# untitled.net
KiCad netlist of a schematic drawn in EAGLE
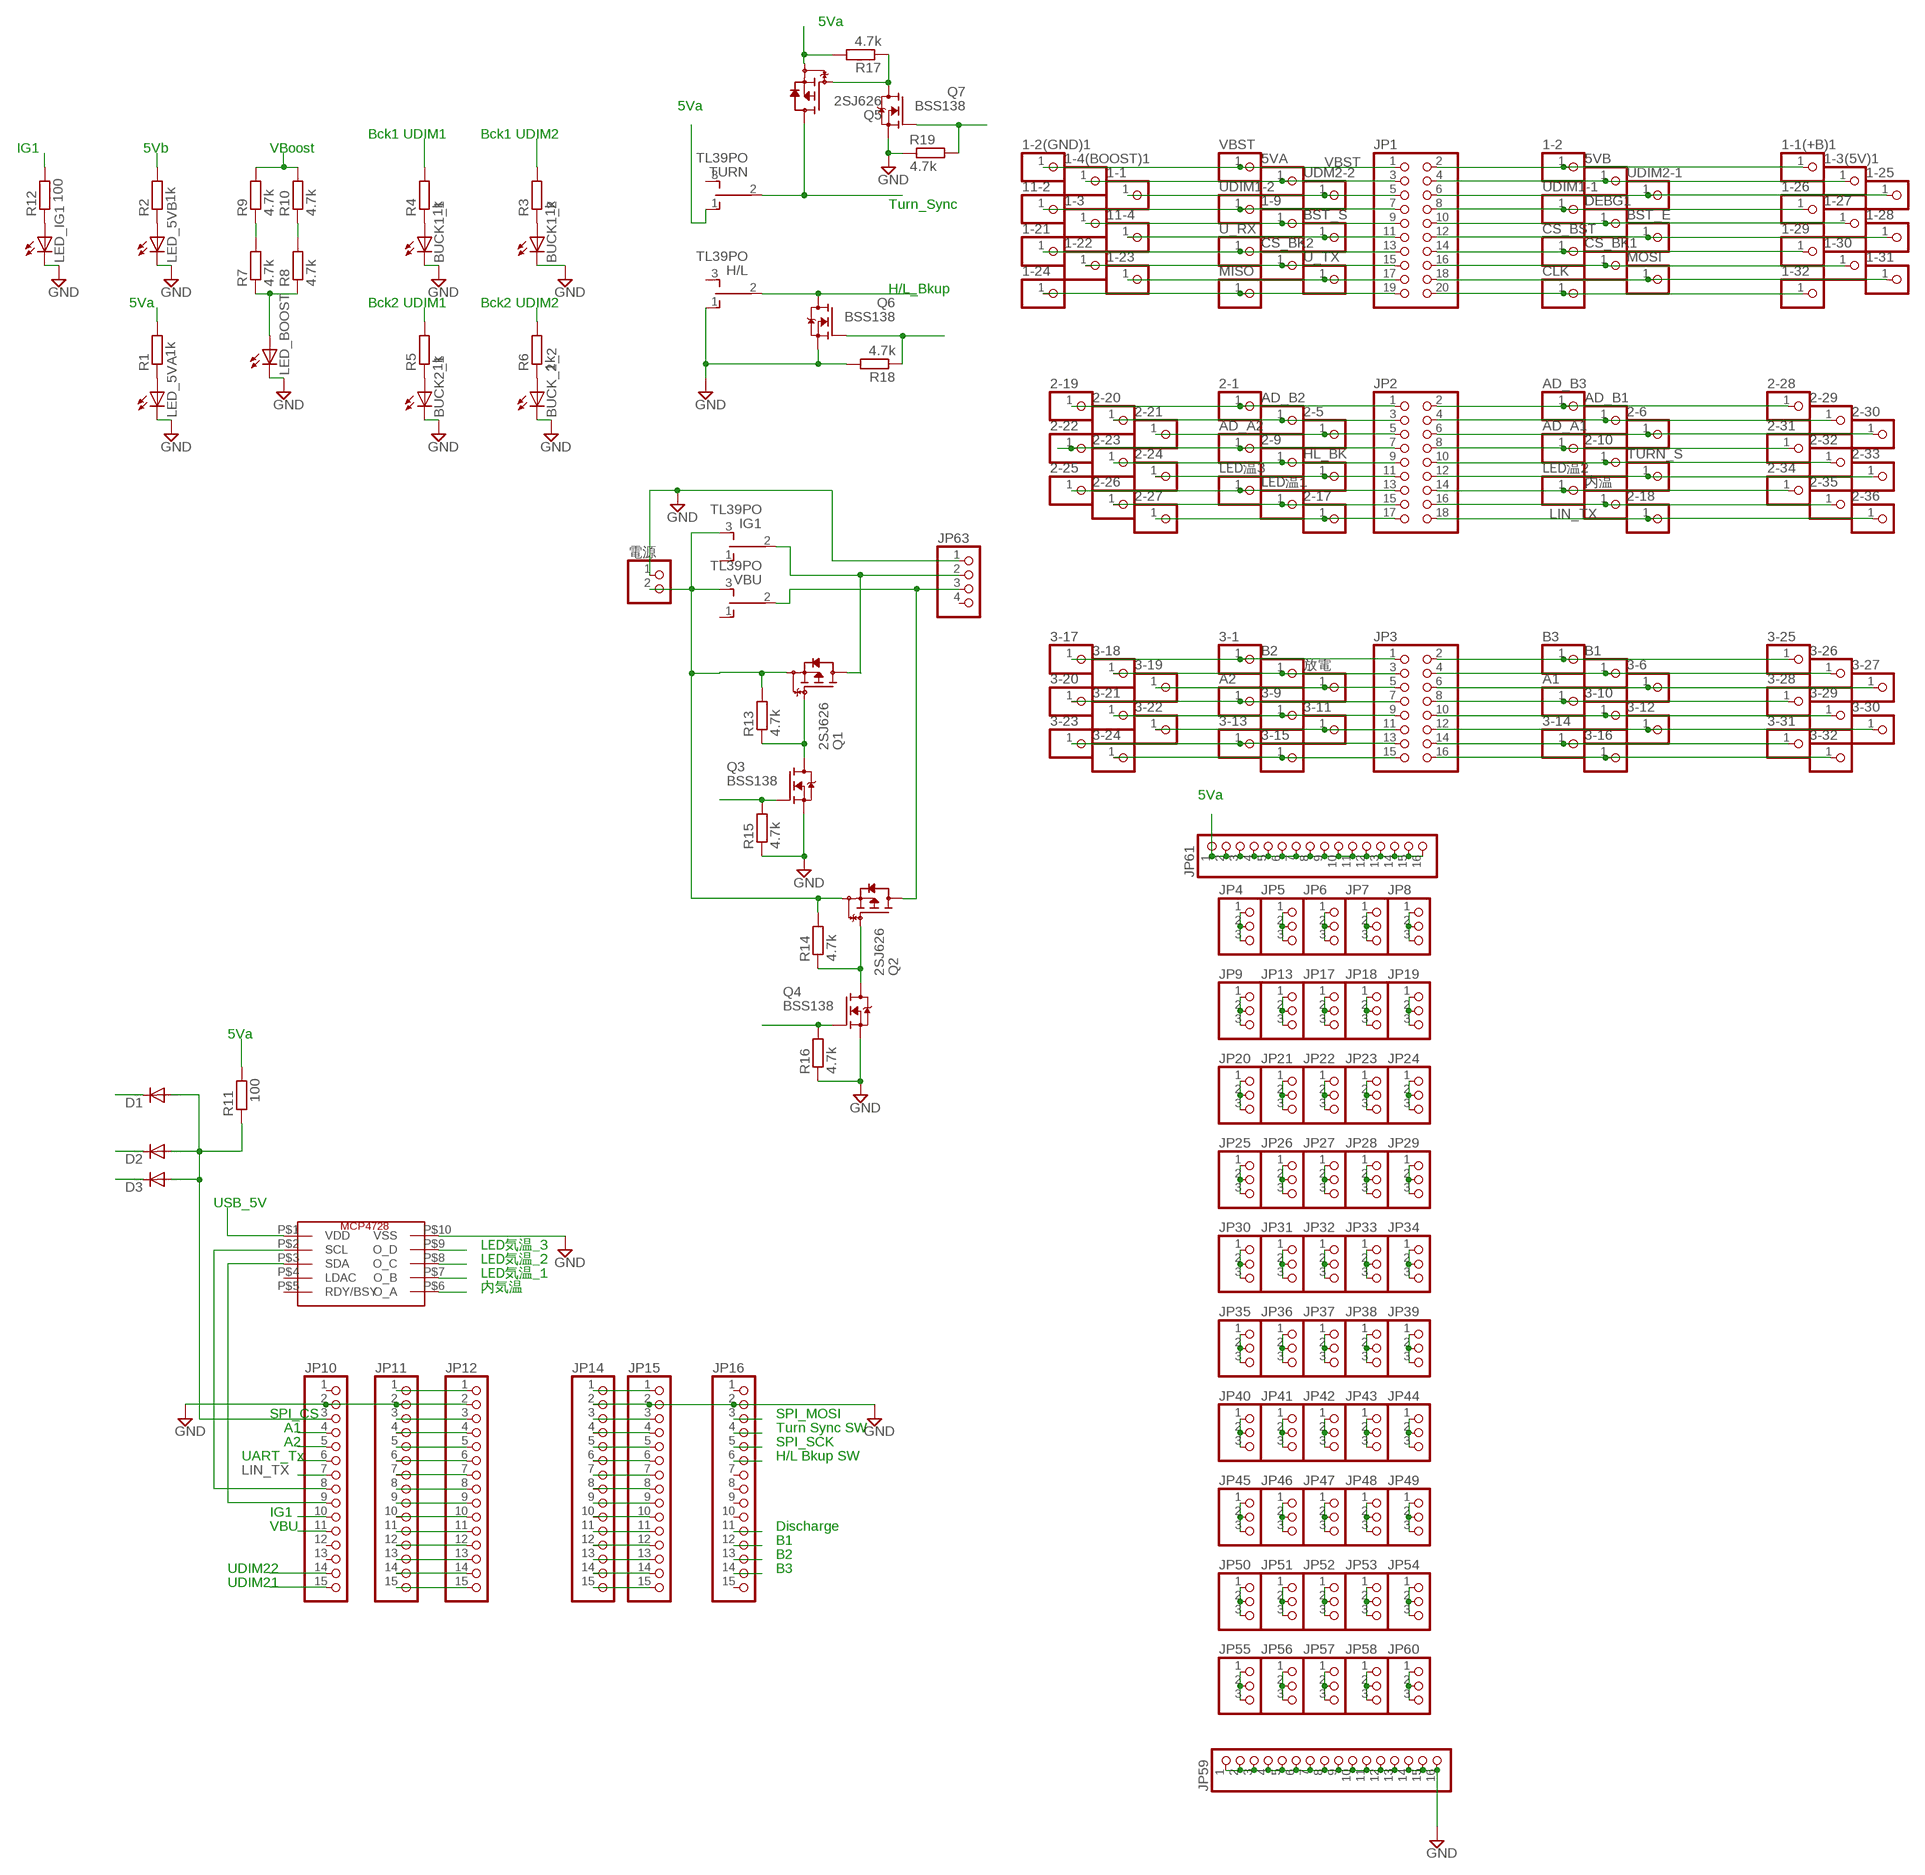
[diagram p0: schematic, sheet 1]

(export (version "E")
  (design (tool "Eeschema 10.0.6"))
  (components
    (comp (ref "1-1")
      (value "PINHD-1X1")
      (footprint "eagle-import:1X01")
      (libsource (lib "eagle-import") (part "PINHD-1X1"))
    )
    (comp (ref "1-1(+B)1")
      (value "PINHD-1X1")
      (footprint "eagle-import:1X01")
      (libsource (lib "eagle-import") (part "PINHD-1X1"))
    )
    (comp (ref "1-2")
      (value "PINHD-1X1")
      (footprint "eagle-import:1X01")
      (libsource (lib "eagle-import") (part "PINHD-1X1"))
    )
    (comp (ref "1-2(GND)1")
      (value "PINHD-1X1")
      (footprint "eagle-import:1X01")
      (libsource (lib "eagle-import") (part "PINHD-1X1"))
    )
    (comp (ref "1-3")
      (value "PINHD-1X1")
      (footprint "eagle-import:1X01")
      (libsource (lib "eagle-import") (part "PINHD-1X1"))
    )
    (comp (ref "1-3(5V)1")
      (value "PINHD-1X1")
      (footprint "eagle-import:1X01")
      (libsource (lib "eagle-import") (part "PINHD-1X1"))
    )
    (comp (ref "1-4(BOOST)1")
      (value "PINHD-1X1")
      (footprint "eagle-import:1X01")
      (libsource (lib "eagle-import") (part "PINHD-1X1"))
    )
    (comp (ref "1-9")
      (value "PINHD-1X1")
      (footprint "eagle-import:1X01")
      (libsource (lib "eagle-import") (part "PINHD-1X1"))
    )
    (comp (ref "1-21")
      (value "PINHD-1X1")
      (footprint "eagle-import:1X01")
      (libsource (lib "eagle-import") (part "PINHD-1X1"))
    )
    (comp (ref "1-22")
      (value "PINHD-1X1")
      (footprint "eagle-import:1X01")
      (libsource (lib "eagle-import") (part "PINHD-1X1"))
    )
    (comp (ref "1-23")
      (value "PINHD-1X1")
      (footprint "eagle-import:1X01")
      (libsource (lib "eagle-import") (part "PINHD-1X1"))
    )
    (comp (ref "1-24")
      (value "PINHD-1X1")
      (footprint "eagle-import:1X01")
      (libsource (lib "eagle-import") (part "PINHD-1X1"))
    )
    (comp (ref "1-25")
      (value "PINHD-1X1")
      (footprint "eagle-import:1X01")
      (libsource (lib "eagle-import") (part "PINHD-1X1"))
    )
    (comp (ref "1-26")
      (value "PINHD-1X1")
      (footprint "eagle-import:1X01")
      (libsource (lib "eagle-import") (part "PINHD-1X1"))
    )
    (comp (ref "1-27")
      (value "PINHD-1X1")
      (footprint "eagle-import:1X01")
      (libsource (lib "eagle-import") (part "PINHD-1X1"))
    )
    (comp (ref "1-28")
      (value "PINHD-1X1")
      (footprint "eagle-import:1X01")
      (libsource (lib "eagle-import") (part "PINHD-1X1"))
    )
    (comp (ref "1-29")
      (value "PINHD-1X1")
      (footprint "eagle-import:1X01")
      (libsource (lib "eagle-import") (part "PINHD-1X1"))
    )
    (comp (ref "1-30")
      (value "PINHD-1X1")
      (footprint "eagle-import:1X01")
      (libsource (lib "eagle-import") (part "PINHD-1X1"))
    )
    (comp (ref "1-31")
      (value "PINHD-1X1")
      (footprint "eagle-import:1X01")
      (libsource (lib "eagle-import") (part "PINHD-1X1"))
    )
    (comp (ref "1-32")
      (value "PINHD-1X1")
      (footprint "eagle-import:1X01")
      (libsource (lib "eagle-import") (part "PINHD-1X1"))
    )
    (comp (ref "2-1")
      (value "PINHD-1X1")
      (footprint "eagle-import:1X01")
      (libsource (lib "eagle-import") (part "PINHD-1X1"))
    )
    (comp (ref "2-5")
      (value "PINHD-1X1")
      (footprint "eagle-import:1X01")
      (libsource (lib "eagle-import") (part "PINHD-1X1"))
    )
    (comp (ref "2-6")
      (value "PINHD-1X1")
      (footprint "eagle-import:1X01")
      (libsource (lib "eagle-import") (part "PINHD-1X1"))
    )
    (comp (ref "2-9")
      (value "PINHD-1X1")
      (footprint "eagle-import:1X01")
      (libsource (lib "eagle-import") (part "PINHD-1X1"))
    )
    (comp (ref "2-10")
      (value "PINHD-1X1")
      (footprint "eagle-import:1X01")
      (libsource (lib "eagle-import") (part "PINHD-1X1"))
    )
    (comp (ref "2-17")
      (value "PINHD-1X1")
      (footprint "eagle-import:1X01")
      (libsource (lib "eagle-import") (part "PINHD-1X1"))
    )
    (comp (ref "2-18")
      (value "PINHD-1X1")
      (footprint "eagle-import:1X01")
      (libsource (lib "eagle-import") (part "PINHD-1X1"))
    )
    (comp (ref "2-19")
      (value "PINHD-1X1")
      (footprint "eagle-import:1X01")
      (libsource (lib "eagle-import") (part "PINHD-1X1"))
    )
    (comp (ref "2-20")
      (value "PINHD-1X1")
      (footprint "eagle-import:1X01")
      (libsource (lib "eagle-import") (part "PINHD-1X1"))
    )
    (comp (ref "2-21")
      (value "PINHD-1X1")
      (footprint "eagle-import:1X01")
      (libsource (lib "eagle-import") (part "PINHD-1X1"))
    )
    (comp (ref "2-22")
      (value "PINHD-1X1")
      (footprint "eagle-import:1X01")
      (libsource (lib "eagle-import") (part "PINHD-1X1"))
    )
    (comp (ref "2-23")
      (value "PINHD-1X1")
      (footprint "eagle-import:1X01")
      (libsource (lib "eagle-import") (part "PINHD-1X1"))
    )
    (comp (ref "2-24")
      (value "PINHD-1X1")
      (footprint "eagle-import:1X01")
      (libsource (lib "eagle-import") (part "PINHD-1X1"))
    )
    (comp (ref "2-25")
      (value "PINHD-1X1")
      (footprint "eagle-import:1X01")
      (libsource (lib "eagle-import") (part "PINHD-1X1"))
    )
    (comp (ref "2-26")
      (value "PINHD-1X1")
      (footprint "eagle-import:1X01")
      (libsource (lib "eagle-import") (part "PINHD-1X1"))
    )
    (comp (ref "2-27")
      (value "PINHD-1X1")
      (footprint "eagle-import:1X01")
      (libsource (lib "eagle-import") (part "PINHD-1X1"))
    )
    (comp (ref "2-28")
      (value "PINHD-1X1")
      (footprint "eagle-import:1X01")
      (libsource (lib "eagle-import") (part "PINHD-1X1"))
    )
    (comp (ref "2-29")
      (value "PINHD-1X1")
      (footprint "eagle-import:1X01")
      (libsource (lib "eagle-import") (part "PINHD-1X1"))
    )
    (comp (ref "2-30")
      (value "PINHD-1X1")
      (footprint "eagle-import:1X01")
      (libsource (lib "eagle-import") (part "PINHD-1X1"))
    )
    (comp (ref "2-31")
      (value "PINHD-1X1")
      (footprint "eagle-import:1X01")
      (libsource (lib "eagle-import") (part "PINHD-1X1"))
    )
    (comp (ref "2-32")
      (value "PINHD-1X1")
      (footprint "eagle-import:1X01")
      (libsource (lib "eagle-import") (part "PINHD-1X1"))
    )
    (comp (ref "2-33")
      (value "PINHD-1X1")
      (footprint "eagle-import:1X01")
      (libsource (lib "eagle-import") (part "PINHD-1X1"))
    )
    (comp (ref "2-34")
      (value "PINHD-1X1")
      (footprint "eagle-import:1X01")
      (libsource (lib "eagle-import") (part "PINHD-1X1"))
    )
    (comp (ref "2-35")
      (value "PINHD-1X1")
      (footprint "eagle-import:1X01")
      (libsource (lib "eagle-import") (part "PINHD-1X1"))
    )
    (comp (ref "2-36")
      (value "PINHD-1X1")
      (footprint "eagle-import:1X01")
      (libsource (lib "eagle-import") (part "PINHD-1X1"))
    )
    (comp (ref "3-1")
      (value "PINHD-1X1")
      (footprint "eagle-import:1X01")
      (libsource (lib "eagle-import") (part "PINHD-1X1"))
    )
    (comp (ref "3-6")
      (value "PINHD-1X1")
      (footprint "eagle-import:1X01")
      (libsource (lib "eagle-import") (part "PINHD-1X1"))
    )
    (comp (ref "3-9")
      (value "PINHD-1X1")
      (footprint "eagle-import:1X01")
      (libsource (lib "eagle-import") (part "PINHD-1X1"))
    )
    (comp (ref "3-10")
      (value "PINHD-1X1")
      (footprint "eagle-import:1X01")
      (libsource (lib "eagle-import") (part "PINHD-1X1"))
    )
    (comp (ref "3-11")
      (value "PINHD-1X1")
      (footprint "eagle-import:1X01")
      (libsource (lib "eagle-import") (part "PINHD-1X1"))
    )
    (comp (ref "3-12")
      (value "PINHD-1X1")
      (footprint "eagle-import:1X01")
      (libsource (lib "eagle-import") (part "PINHD-1X1"))
    )
    (comp (ref "3-13")
      (value "PINHD-1X1")
      (footprint "eagle-import:1X01")
      (libsource (lib "eagle-import") (part "PINHD-1X1"))
    )
    (comp (ref "3-14")
      (value "PINHD-1X1")
      (footprint "eagle-import:1X01")
      (libsource (lib "eagle-import") (part "PINHD-1X1"))
    )
    (comp (ref "3-15")
      (value "PINHD-1X1")
      (footprint "eagle-import:1X01")
      (libsource (lib "eagle-import") (part "PINHD-1X1"))
    )
    (comp (ref "3-16")
      (value "PINHD-1X1")
      (footprint "eagle-import:1X01")
      (libsource (lib "eagle-import") (part "PINHD-1X1"))
    )
    (comp (ref "3-17")
      (value "PINHD-1X1")
      (footprint "eagle-import:1X01")
      (libsource (lib "eagle-import") (part "PINHD-1X1"))
    )
    (comp (ref "3-18")
      (value "PINHD-1X1")
      (footprint "eagle-import:1X01")
      (libsource (lib "eagle-import") (part "PINHD-1X1"))
    )
    (comp (ref "3-19")
      (value "PINHD-1X1")
      (footprint "eagle-import:1X01")
      (libsource (lib "eagle-import") (part "PINHD-1X1"))
    )
    (comp (ref "3-20")
      (value "PINHD-1X1")
      (footprint "eagle-import:1X01")
      (libsource (lib "eagle-import") (part "PINHD-1X1"))
    )
    (comp (ref "3-21")
      (value "PINHD-1X1")
      (footprint "eagle-import:1X01")
      (libsource (lib "eagle-import") (part "PINHD-1X1"))
    )
    (comp (ref "3-22")
      (value "PINHD-1X1")
      (footprint "eagle-import:1X01")
      (libsource (lib "eagle-import") (part "PINHD-1X1"))
    )
    (comp (ref "3-23")
      (value "PINHD-1X1")
      (footprint "eagle-import:1X01")
      (libsource (lib "eagle-import") (part "PINHD-1X1"))
    )
    (comp (ref "3-24")
      (value "PINHD-1X1")
      (footprint "eagle-import:1X01")
      (libsource (lib "eagle-import") (part "PINHD-1X1"))
    )
    (comp (ref "3-25")
      (value "PINHD-1X1")
      (footprint "eagle-import:1X01")
      (libsource (lib "eagle-import") (part "PINHD-1X1"))
    )
    (comp (ref "3-26")
      (value "PINHD-1X1")
      (footprint "eagle-import:1X01")
      (libsource (lib "eagle-import") (part "PINHD-1X1"))
    )
    (comp (ref "3-27")
      (value "PINHD-1X1")
      (footprint "eagle-import:1X01")
      (libsource (lib "eagle-import") (part "PINHD-1X1"))
    )
    (comp (ref "3-28")
      (value "PINHD-1X1")
      (footprint "eagle-import:1X01")
      (libsource (lib "eagle-import") (part "PINHD-1X1"))
    )
    (comp (ref "3-29")
      (value "PINHD-1X1")
      (footprint "eagle-import:1X01")
      (libsource (lib "eagle-import") (part "PINHD-1X1"))
    )
    (comp (ref "3-30")
      (value "PINHD-1X1")
      (footprint "eagle-import:1X01")
      (libsource (lib "eagle-import") (part "PINHD-1X1"))
    )
    (comp (ref "3-31")
      (value "PINHD-1X1")
      (footprint "eagle-import:1X01")
      (libsource (lib "eagle-import") (part "PINHD-1X1"))
    )
    (comp (ref "3-32")
      (value "PINHD-1X1")
      (footprint "eagle-import:1X01")
      (libsource (lib "eagle-import") (part "PINHD-1X1"))
    )
    (comp (ref "5VA")
      (value "PINHD-1X1")
      (footprint "eagle-import:1X01")
      (libsource (lib "eagle-import") (part "PINHD-1X1"))
    )
    (comp (ref "5VB")
      (value "PINHD-1X1")
      (footprint "eagle-import:1X01")
      (libsource (lib "eagle-import") (part "PINHD-1X1"))
    )
    (comp (ref "11-2")
      (value "PINHD-1X1")
      (footprint "eagle-import:1X01")
      (libsource (lib "eagle-import") (part "PINHD-1X1"))
    )
    (comp (ref "11-4")
      (value "PINHD-1X1")
      (footprint "eagle-import:1X01")
      (libsource (lib "eagle-import") (part "PINHD-1X1"))
    )
    (comp (ref "A1")
      (value "PINHD-1X1")
      (footprint "eagle-import:1X01")
      (libsource (lib "eagle-import") (part "PINHD-1X1"))
    )
    (comp (ref "A2")
      (value "PINHD-1X1")
      (footprint "eagle-import:1X01")
      (libsource (lib "eagle-import") (part "PINHD-1X1"))
    )
    (comp (ref "AD_A1")
      (value "PINHD-1X1")
      (footprint "eagle-import:1X01")
      (libsource (lib "eagle-import") (part "PINHD-1X1"))
    )
    (comp (ref "AD_A2")
      (value "PINHD-1X1")
      (footprint "eagle-import:1X01")
      (libsource (lib "eagle-import") (part "PINHD-1X1"))
    )
    (comp (ref "AD_B1")
      (value "PINHD-1X1")
      (footprint "eagle-import:1X01")
      (libsource (lib "eagle-import") (part "PINHD-1X1"))
    )
    (comp (ref "AD_B2")
      (value "PINHD-1X1")
      (footprint "eagle-import:1X01")
      (libsource (lib "eagle-import") (part "PINHD-1X1"))
    )
    (comp (ref "AD_B3")
      (value "PINHD-1X1")
      (footprint "eagle-import:1X01")
      (libsource (lib "eagle-import") (part "PINHD-1X1"))
    )
    (comp (ref "B1")
      (value "PINHD-1X1")
      (footprint "eagle-import:1X01")
      (libsource (lib "eagle-import") (part "PINHD-1X1"))
    )
    (comp (ref "B2")
      (value "PINHD-1X1")
      (footprint "eagle-import:1X01")
      (libsource (lib "eagle-import") (part "PINHD-1X1"))
    )
    (comp (ref "B3")
      (value "PINHD-1X1")
      (footprint "eagle-import:1X01")
      (libsource (lib "eagle-import") (part "PINHD-1X1"))
    )
    (comp (ref "BST_E")
      (value "PINHD-1X1")
      (footprint "eagle-import:1X01")
      (libsource (lib "eagle-import") (part "PINHD-1X1"))
    )
    (comp (ref "BST_S")
      (value "PINHD-1X1")
      (footprint "eagle-import:1X01")
      (libsource (lib "eagle-import") (part "PINHD-1X1"))
    )
    (comp (ref "BUCK1_1")
      (value "LEDCHIP-LED0603")
      (footprint "eagle-import:CHIP-LED0603")
      (libsource (lib "eagle-import") (part "LEDCHIP-LED0603"))
    )
    (comp (ref "BUCK1_2")
      (value "LEDCHIP-LED0603")
      (footprint "eagle-import:CHIP-LED0603")
      (libsource (lib "eagle-import") (part "LEDCHIP-LED0603"))
    )
    (comp (ref "BUCK2_1")
      (value "LEDCHIP-LED0603")
      (footprint "eagle-import:CHIP-LED0603")
      (libsource (lib "eagle-import") (part "LEDCHIP-LED0603"))
    )
    (comp (ref "BUCK_2_2")
      (value "LEDCHIP-LED0603")
      (footprint "eagle-import:CHIP-LED0603")
      (libsource (lib "eagle-import") (part "LEDCHIP-LED0603"))
    )
    (comp (ref "CLK")
      (value "PINHD-1X1")
      (footprint "eagle-import:1X01")
      (libsource (lib "eagle-import") (part "PINHD-1X1"))
    )
    (comp (ref "CS_BK1")
      (value "PINHD-1X1")
      (footprint "eagle-import:1X01")
      (libsource (lib "eagle-import") (part "PINHD-1X1"))
    )
    (comp (ref "CS_BK2")
      (value "PINHD-1X1")
      (footprint "eagle-import:1X01")
      (libsource (lib "eagle-import") (part "PINHD-1X1"))
    )
    (comp (ref "CS_BST")
      (value "PINHD-1X1")
      (footprint "eagle-import:1X01")
      (libsource (lib "eagle-import") (part "PINHD-1X1"))
    )
    (comp (ref "D1")
      (value "DIODE-SOD523")
      (footprint "eagle-import:SOD523")
      (libsource (lib "eagle-import") (part "DIODE-SOD523"))
    )
    (comp (ref "D2")
      (value "DIODE-SOD523")
      (footprint "eagle-import:SOD523")
      (libsource (lib "eagle-import") (part "DIODE-SOD523"))
    )
    (comp (ref "D3")
      (value "DIODE-SOD523")
      (footprint "eagle-import:SOD523")
      (libsource (lib "eagle-import") (part "DIODE-SOD523"))
    )
    (comp (ref "DEBG1")
      (value "PINHD-1X1")
      (footprint "eagle-import:1X01")
      (libsource (lib "eagle-import") (part "PINHD-1X1"))
    )
    (comp (ref "H/L")
      (value "TL39PO")
      (footprint "eagle-import:TL3XPO")
      (libsource (lib "eagle-import") (part "TL39PO"))
    )
    (comp (ref "HL_BK")
      (value "PINHD-1X1")
      (footprint "eagle-import:1X01")
      (libsource (lib "eagle-import") (part "PINHD-1X1"))
    )
    (comp (ref "IG1")
      (value "TL39PO")
      (footprint "eagle-import:TL3XPO")
      (libsource (lib "eagle-import") (part "TL39PO"))
    )
    (comp (ref "JP1")
      (value "PINHD-2X10")
      (footprint "eagle-import:2X10")
      (libsource (lib "eagle-import") (part "PINHD-2X10"))
    )
    (comp (ref "JP2")
      (value "PINHD-2X9")
      (footprint "eagle-import:2X09")
      (libsource (lib "eagle-import") (part "PINHD-2X9"))
    )
    (comp (ref "JP3")
      (value "PINHD-2X8")
      (footprint "eagle-import:2X08")
      (libsource (lib "eagle-import") (part "PINHD-2X8"))
    )
    (comp (ref "JP4")
      (value "PINHD-1X3")
      (footprint "eagle-import:1X03")
      (libsource (lib "eagle-import") (part "PINHD-1X3"))
    )
    (comp (ref "JP5")
      (value "PINHD-1X3")
      (footprint "eagle-import:1X03")
      (libsource (lib "eagle-import") (part "PINHD-1X3"))
    )
    (comp (ref "JP6")
      (value "PINHD-1X3")
      (footprint "eagle-import:1X03")
      (libsource (lib "eagle-import") (part "PINHD-1X3"))
    )
    (comp (ref "JP7")
      (value "PINHD-1X3")
      (footprint "eagle-import:1X03")
      (libsource (lib "eagle-import") (part "PINHD-1X3"))
    )
    (comp (ref "JP8")
      (value "PINHD-1X3")
      (footprint "eagle-import:1X03")
      (libsource (lib "eagle-import") (part "PINHD-1X3"))
    )
    (comp (ref "JP9")
      (value "PINHD-1X3")
      (footprint "eagle-import:1X03")
      (libsource (lib "eagle-import") (part "PINHD-1X3"))
    )
    (comp (ref "JP10")
      (value "PINHD-1X15")
      (footprint "eagle-import:1X15")
      (libsource (lib "eagle-import") (part "PINHD-1X15"))
    )
    (comp (ref "JP11")
      (value "PINHD-1X15")
      (footprint "eagle-import:1X15")
      (libsource (lib "eagle-import") (part "PINHD-1X15"))
    )
    (comp (ref "JP12")
      (value "PINHD-1X15")
      (footprint "eagle-import:1X15")
      (libsource (lib "eagle-import") (part "PINHD-1X15"))
    )
    (comp (ref "JP13")
      (value "PINHD-1X3")
      (footprint "eagle-import:1X03")
      (libsource (lib "eagle-import") (part "PINHD-1X3"))
    )
    (comp (ref "JP14")
      (value "PINHD-1X15")
      (footprint "eagle-import:1X15")
      (libsource (lib "eagle-import") (part "PINHD-1X15"))
    )
    (comp (ref "JP15")
      (value "PINHD-1X15")
      (footprint "eagle-import:1X15")
      (libsource (lib "eagle-import") (part "PINHD-1X15"))
    )
    (comp (ref "JP16")
      (value "PINHD-1X15")
      (footprint "eagle-import:1X15")
      (libsource (lib "eagle-import") (part "PINHD-1X15"))
    )
    (comp (ref "JP17")
      (value "PINHD-1X3")
      (footprint "eagle-import:1X03")
      (libsource (lib "eagle-import") (part "PINHD-1X3"))
    )
    (comp (ref "JP18")
      (value "PINHD-1X3")
      (footprint "eagle-import:1X03")
      (libsource (lib "eagle-import") (part "PINHD-1X3"))
    )
    (comp (ref "JP19")
      (value "PINHD-1X3")
      (footprint "eagle-import:1X03")
      (libsource (lib "eagle-import") (part "PINHD-1X3"))
    )
    (comp (ref "JP20")
      (value "PINHD-1X3")
      (footprint "eagle-import:1X03")
      (libsource (lib "eagle-import") (part "PINHD-1X3"))
    )
    (comp (ref "JP21")
      (value "PINHD-1X3")
      (footprint "eagle-import:1X03")
      (libsource (lib "eagle-import") (part "PINHD-1X3"))
    )
    (comp (ref "JP22")
      (value "PINHD-1X3")
      (footprint "eagle-import:1X03")
      (libsource (lib "eagle-import") (part "PINHD-1X3"))
    )
    (comp (ref "JP23")
      (value "PINHD-1X3")
      (footprint "eagle-import:1X03")
      (libsource (lib "eagle-import") (part "PINHD-1X3"))
    )
    (comp (ref "JP24")
      (value "PINHD-1X3")
      (footprint "eagle-import:1X03")
      (libsource (lib "eagle-import") (part "PINHD-1X3"))
    )
    (comp (ref "JP25")
      (value "PINHD-1X3")
      (footprint "eagle-import:1X03")
      (libsource (lib "eagle-import") (part "PINHD-1X3"))
    )
    (comp (ref "JP26")
      (value "PINHD-1X3")
      (footprint "eagle-import:1X03")
      (libsource (lib "eagle-import") (part "PINHD-1X3"))
    )
    (comp (ref "JP27")
      (value "PINHD-1X3")
      (footprint "eagle-import:1X03")
      (libsource (lib "eagle-import") (part "PINHD-1X3"))
    )
    (comp (ref "JP28")
      (value "PINHD-1X3")
      (footprint "eagle-import:1X03")
      (libsource (lib "eagle-import") (part "PINHD-1X3"))
    )
    (comp (ref "JP29")
      (value "PINHD-1X3")
      (footprint "eagle-import:1X03")
      (libsource (lib "eagle-import") (part "PINHD-1X3"))
    )
    (comp (ref "JP30")
      (value "PINHD-1X3")
      (footprint "eagle-import:1X03")
      (libsource (lib "eagle-import") (part "PINHD-1X3"))
    )
    (comp (ref "JP31")
      (value "PINHD-1X3")
      (footprint "eagle-import:1X03")
      (libsource (lib "eagle-import") (part "PINHD-1X3"))
    )
    (comp (ref "JP32")
      (value "PINHD-1X3")
      (footprint "eagle-import:1X03")
      (libsource (lib "eagle-import") (part "PINHD-1X3"))
    )
    (comp (ref "JP33")
      (value "PINHD-1X3")
      (footprint "eagle-import:1X03")
      (libsource (lib "eagle-import") (part "PINHD-1X3"))
    )
    (comp (ref "JP34")
      (value "PINHD-1X3")
      (footprint "eagle-import:1X03")
      (libsource (lib "eagle-import") (part "PINHD-1X3"))
    )
    (comp (ref "JP35")
      (value "PINHD-1X3")
      (footprint "eagle-import:1X03")
      (libsource (lib "eagle-import") (part "PINHD-1X3"))
    )
    (comp (ref "JP36")
      (value "PINHD-1X3")
      (footprint "eagle-import:1X03")
      (libsource (lib "eagle-import") (part "PINHD-1X3"))
    )
    (comp (ref "JP37")
      (value "PINHD-1X3")
      (footprint "eagle-import:1X03")
      (libsource (lib "eagle-import") (part "PINHD-1X3"))
    )
    (comp (ref "JP38")
      (value "PINHD-1X3")
      (footprint "eagle-import:1X03")
      (libsource (lib "eagle-import") (part "PINHD-1X3"))
    )
    (comp (ref "JP39")
      (value "PINHD-1X3")
      (footprint "eagle-import:1X03")
      (libsource (lib "eagle-import") (part "PINHD-1X3"))
    )
    (comp (ref "JP40")
      (value "PINHD-1X3")
      (footprint "eagle-import:1X03")
      (libsource (lib "eagle-import") (part "PINHD-1X3"))
    )
    (comp (ref "JP41")
      (value "PINHD-1X3")
      (footprint "eagle-import:1X03")
      (libsource (lib "eagle-import") (part "PINHD-1X3"))
    )
    (comp (ref "JP42")
      (value "PINHD-1X3")
      (footprint "eagle-import:1X03")
      (libsource (lib "eagle-import") (part "PINHD-1X3"))
    )
    (comp (ref "JP43")
      (value "PINHD-1X3")
      (footprint "eagle-import:1X03")
      (libsource (lib "eagle-import") (part "PINHD-1X3"))
    )
    (comp (ref "JP44")
      (value "PINHD-1X3")
      (footprint "eagle-import:1X03")
      (libsource (lib "eagle-import") (part "PINHD-1X3"))
    )
    (comp (ref "JP45")
      (value "PINHD-1X3")
      (footprint "eagle-import:1X03")
      (libsource (lib "eagle-import") (part "PINHD-1X3"))
    )
    (comp (ref "JP46")
      (value "PINHD-1X3")
      (footprint "eagle-import:1X03")
      (libsource (lib "eagle-import") (part "PINHD-1X3"))
    )
    (comp (ref "JP47")
      (value "PINHD-1X3")
      (footprint "eagle-import:1X03")
      (libsource (lib "eagle-import") (part "PINHD-1X3"))
    )
    (comp (ref "JP48")
      (value "PINHD-1X3")
      (footprint "eagle-import:1X03")
      (libsource (lib "eagle-import") (part "PINHD-1X3"))
    )
    (comp (ref "JP49")
      (value "PINHD-1X3")
      (footprint "eagle-import:1X03")
      (libsource (lib "eagle-import") (part "PINHD-1X3"))
    )
    (comp (ref "JP50")
      (value "PINHD-1X3")
      (footprint "eagle-import:1X03")
      (libsource (lib "eagle-import") (part "PINHD-1X3"))
    )
    (comp (ref "JP51")
      (value "PINHD-1X3")
      (footprint "eagle-import:1X03")
      (libsource (lib "eagle-import") (part "PINHD-1X3"))
    )
    (comp (ref "JP52")
      (value "PINHD-1X3")
      (footprint "eagle-import:1X03")
      (libsource (lib "eagle-import") (part "PINHD-1X3"))
    )
    (comp (ref "JP53")
      (value "PINHD-1X3")
      (footprint "eagle-import:1X03")
      (libsource (lib "eagle-import") (part "PINHD-1X3"))
    )
    (comp (ref "JP54")
      (value "PINHD-1X3")
      (footprint "eagle-import:1X03")
      (libsource (lib "eagle-import") (part "PINHD-1X3"))
    )
    (comp (ref "JP55")
      (value "PINHD-1X3")
      (footprint "eagle-import:1X03")
      (libsource (lib "eagle-import") (part "PINHD-1X3"))
    )
    (comp (ref "JP56")
      (value "PINHD-1X3")
      (footprint "eagle-import:1X03")
      (libsource (lib "eagle-import") (part "PINHD-1X3"))
    )
    (comp (ref "JP57")
      (value "PINHD-1X3")
      (footprint "eagle-import:1X03")
      (libsource (lib "eagle-import") (part "PINHD-1X3"))
    )
    (comp (ref "JP58")
      (value "PINHD-1X3")
      (footprint "eagle-import:1X03")
      (libsource (lib "eagle-import") (part "PINHD-1X3"))
    )
    (comp (ref "JP59")
      (value "PINHD-1X16")
      (footprint "eagle-import:1X16")
      (libsource (lib "eagle-import") (part "PINHD-1X16"))
    )
    (comp (ref "JP60")
      (value "PINHD-1X3")
      (footprint "eagle-import:1X03")
      (libsource (lib "eagle-import") (part "PINHD-1X3"))
    )
    (comp (ref "JP61")
      (value "PINHD-1X16")
      (footprint "eagle-import:1X16")
      (libsource (lib "eagle-import") (part "PINHD-1X16"))
    )
    (comp (ref "JP63")
      (value "PINHD-1X4")
      (footprint "eagle-import:1X04")
      (libsource (lib "eagle-import") (part "PINHD-1X4"))
    )
    (comp (ref "LED_5VA")
      (value "LEDCHIP-LED0603")
      (footprint "eagle-import:CHIP-LED0603")
      (libsource (lib "eagle-import") (part "LEDCHIP-LED0603"))
    )
    (comp (ref "LED_5VB")
      (value "LEDCHIP-LED0603")
      (footprint "eagle-import:CHIP-LED0603")
      (libsource (lib "eagle-import") (part "LEDCHIP-LED0603"))
    )
    (comp (ref "LED_BOOST")
      (value "LEDCHIP-LED0603")
      (footprint "eagle-import:CHIP-LED0603")
      (libsource (lib "eagle-import") (part "LEDCHIP-LED0603"))
    )
    (comp (ref "LED_IG1")
      (value "LEDCHIP-LED0603")
      (footprint "eagle-import:CHIP-LED0603")
      (libsource (lib "eagle-import") (part "LEDCHIP-LED0603"))
    )
    (comp (ref "LED温1")
      (value "PINHD-1X1")
      (footprint "eagle-import:1X01")
      (libsource (lib "eagle-import") (part "PINHD-1X1"))
    )
    (comp (ref "LED温2")
      (value "PINHD-1X1")
      (footprint "eagle-import:1X01")
      (libsource (lib "eagle-import") (part "PINHD-1X1"))
    )
    (comp (ref "LED温3")
      (value "PINHD-1X1")
      (footprint "eagle-import:1X01")
      (libsource (lib "eagle-import") (part "PINHD-1X1"))
    )
    (comp (ref "MISO")
      (value "PINHD-1X1")
      (footprint "eagle-import:1X01")
      (libsource (lib "eagle-import") (part "PINHD-1X1"))
    )
    (comp (ref "MOSI")
      (value "PINHD-1X1")
      (footprint "eagle-import:1X01")
      (libsource (lib "eagle-import") (part "PINHD-1X1"))
    )
    (comp (ref "Q1")
      (value "2SJ626")
      (footprint "eagle-import:SOT23")
      (fields (field (name "MF") "Fairchild"))
      (libsource (lib "eagle-import") (part "2SJ626"))
    )
    (comp (ref "Q2")
      (value "2SJ626")
      (footprint "eagle-import:SOT23")
      (fields (field (name "MF") "Fairchild"))
      (libsource (lib "eagle-import") (part "2SJ626"))
    )
    (comp (ref "Q3")
      (value "BSS138")
      (footprint "eagle-import:SOT23")
      (fields (field (name "MF") "Fairchild"))
      (libsource (lib "eagle-import") (part "BSS138"))
    )
    (comp (ref "Q4")
      (value "BSS138")
      (footprint "eagle-import:SOT23")
      (fields (field (name "MF") "Fairchild"))
      (libsource (lib "eagle-import") (part "BSS138"))
    )
    (comp (ref "Q5")
      (value "2SJ626")
      (footprint "eagle-import:SOT23")
      (fields (field (name "MF") "Fairchild"))
      (libsource (lib "eagle-import") (part "2SJ626"))
    )
    (comp (ref "Q6")
      (value "BSS138")
      (footprint "eagle-import:SOT23")
      (fields (field (name "MF") "Fairchild"))
      (libsource (lib "eagle-import") (part "BSS138"))
    )
    (comp (ref "Q7")
      (value "BSS138")
      (footprint "eagle-import:SOT23")
      (fields (field (name "MF") "Fairchild"))
      (libsource (lib "eagle-import") (part "BSS138"))
    )
    (comp (ref "R1")
      (value "1k")
      (footprint "eagle-import:R0603")
      (libsource (lib "eagle-import") (part "R-EU_R0603"))
    )
    (comp (ref "R2")
      (value "1k")
      (footprint "eagle-import:R0603")
      (libsource (lib "eagle-import") (part "R-EU_R0603"))
    )
    (comp (ref "R3")
      (value "1k")
      (footprint "eagle-import:R0603")
      (libsource (lib "eagle-import") (part "R-EU_R0603"))
    )
    (comp (ref "R4")
      (value "1k")
      (footprint "eagle-import:R0603")
      (libsource (lib "eagle-import") (part "R-EU_R0603"))
    )
    (comp (ref "R5")
      (value "1k")
      (footprint "eagle-import:R0603")
      (libsource (lib "eagle-import") (part "R-EU_R0603"))
    )
    (comp (ref "R6")
      (value "1k")
      (footprint "eagle-import:R0603")
      (libsource (lib "eagle-import") (part "R-EU_R0603"))
    )
    (comp (ref "R7")
      (value "4.7k")
      (footprint "eagle-import:R0603")
      (libsource (lib "eagle-import") (part "R-EU_R0603"))
    )
    (comp (ref "R8")
      (value "4.7k")
      (footprint "eagle-import:R0603")
      (libsource (lib "eagle-import") (part "R-EU_R0603"))
    )
    (comp (ref "R9")
      (value "4.7k")
      (footprint "eagle-import:R0603")
      (libsource (lib "eagle-import") (part "R-EU_R0603"))
    )
    (comp (ref "R10")
      (value "4.7k")
      (footprint "eagle-import:R0603")
      (libsource (lib "eagle-import") (part "R-EU_R0603"))
    )
    (comp (ref "R11")
      (value "100")
      (footprint "eagle-import:R0603")
      (libsource (lib "eagle-import") (part "R-EU_R0603"))
    )
    (comp (ref "R12")
      (value "100")
      (footprint "eagle-import:R0603")
      (libsource (lib "eagle-import") (part "R-EU_R0603"))
    )
    (comp (ref "R13")
      (value "4.7k")
      (footprint "eagle-import:R0603")
      (libsource (lib "eagle-import") (part "R-EU_R0603"))
    )
    (comp (ref "R14")
      (value "4.7k")
      (footprint "eagle-import:R0603")
      (libsource (lib "eagle-import") (part "R-EU_R0603"))
    )
    (comp (ref "R15")
      (value "4.7k")
      (footprint "eagle-import:R0603")
      (libsource (lib "eagle-import") (part "R-EU_R0603"))
    )
    (comp (ref "R16")
      (value "4.7k")
      (footprint "eagle-import:R0603")
      (libsource (lib "eagle-import") (part "R-EU_R0603"))
    )
    (comp (ref "R17")
      (value "4.7k")
      (footprint "eagle-import:R0603")
      (libsource (lib "eagle-import") (part "R-EU_R0603"))
    )
    (comp (ref "R18")
      (value "4.7k")
      (footprint "eagle-import:R0603")
      (libsource (lib "eagle-import") (part "R-EU_R0603"))
    )
    (comp (ref "R19")
      (value "4.7k")
      (footprint "eagle-import:R0603")
      (libsource (lib "eagle-import") (part "R-EU_R0603"))
    )
    (comp (ref "TURN")
      (value "TL39PO")
      (footprint "eagle-import:TL3XPO")
      (libsource (lib "eagle-import") (part "TL39PO"))
    )
    (comp (ref "TURN_S")
      (value "PINHD-1X1")
      (footprint "eagle-import:1X01")
      (libsource (lib "eagle-import") (part "PINHD-1X1"))
    )
    (comp (ref "U$1")
      (value "MCP4728")
      (footprint "eagle-import:MCP4728")
      (libsource (lib "eagle-import") (part "MCP4728"))
    )
    (comp (ref "UDIM1-1")
      (value "PINHD-1X1")
      (footprint "eagle-import:1X01")
      (libsource (lib "eagle-import") (part "PINHD-1X1"))
    )
    (comp (ref "UDIM1-2")
      (value "PINHD-1X1")
      (footprint "eagle-import:1X01")
      (libsource (lib "eagle-import") (part "PINHD-1X1"))
    )
    (comp (ref "UDIM2-1")
      (value "PINHD-1X1")
      (footprint "eagle-import:1X01")
      (libsource (lib "eagle-import") (part "PINHD-1X1"))
    )
    (comp (ref "UDM2-2")
      (value "PINHD-1X1")
      (footprint "eagle-import:1X01")
      (libsource (lib "eagle-import") (part "PINHD-1X1"))
    )
    (comp (ref "U_RX")
      (value "PINHD-1X1")
      (footprint "eagle-import:1X01")
      (libsource (lib "eagle-import") (part "PINHD-1X1"))
    )
    (comp (ref "U_TX")
      (value "PINHD-1X1")
      (footprint "eagle-import:1X01")
      (libsource (lib "eagle-import") (part "PINHD-1X1"))
    )
    (comp (ref "VBST")
      (value "PINHD-1X1")
      (footprint "eagle-import:1X01")
      (libsource (lib "eagle-import") (part "PINHD-1X1"))
    )
    (comp (ref "VBU")
      (value "TL39PO")
      (footprint "eagle-import:TL3XPO")
      (libsource (lib "eagle-import") (part "TL39PO"))
    )
    (comp (ref "内温")
      (value "PINHD-1X1")
      (footprint "eagle-import:1X01")
      (libsource (lib "eagle-import") (part "PINHD-1X1"))
    )
    (comp (ref "放電")
      (value "PINHD-1X1")
      (footprint "eagle-import:1X01")
      (libsource (lib "eagle-import") (part "PINHD-1X1"))
    )
    (comp (ref "電源")
      (value "PINHD-1X2")
      (footprint "eagle-import:1X02")
      (libsource (lib "eagle-import") (part "PINHD-1X2"))
    )
  )
  (nets
    (net (code "1") (name "/+B(電源)") (class "Default")
      (node (ref "IG1") (pin "3") (pinfunction "S_3") (pintype "passive"))
      (node (ref "Q1") (pin "2") (pinfunction "S_2") (pintype "passive"))
      (node (ref "Q2") (pin "2") (pinfunction "S_2") (pintype "passive"))
      (node (ref "R13") (pin "2") (pinfunction "2_2") (pintype "passive"))
      (node (ref "R14") (pin "2") (pinfunction "2_2") (pintype "passive"))
      (node (ref "VBU") (pin "3") (pinfunction "S_3") (pintype "passive"))
      (node (ref "電源") (pin "2") (pinfunction "2_2") (pintype "passive"))
    )
    (net (code "2") (name "/5VA") (class "Default")
      (node (ref "1-4(BOOST)1") (pin "1") (pinfunction "1_1") (pintype "passive"))
      (node (ref "5VA") (pin "1") (pinfunction "1_1") (pintype "passive"))
      (node (ref "JP1") (pin "3") (pinfunction "3_3") (pintype "passive"))
      (node (ref "JP61") (pin "1") (pinfunction "1_1") (pintype "passive"))
      (node (ref "JP61") (pin "10") (pinfunction "10_10") (pintype "passive"))
      (node (ref "JP61") (pin "11") (pinfunction "11_11") (pintype "passive"))
      (node (ref "JP61") (pin "12") (pinfunction "12_12") (pintype "passive"))
      (node (ref "JP61") (pin "13") (pinfunction "13_13") (pintype "passive"))
      (node (ref "JP61") (pin "14") (pinfunction "14_14") (pintype "passive"))
      (node (ref "JP61") (pin "15") (pinfunction "15_15") (pintype "passive"))
      (node (ref "JP61") (pin "16") (pinfunction "16_16") (pintype "passive"))
      (node (ref "JP61") (pin "2") (pinfunction "2_2") (pintype "passive"))
      (node (ref "JP61") (pin "3") (pinfunction "3_3") (pintype "passive"))
      (node (ref "JP61") (pin "4") (pinfunction "4_4") (pintype "passive"))
      (node (ref "JP61") (pin "5") (pinfunction "5_5") (pintype "passive"))
      (node (ref "JP61") (pin "6") (pinfunction "6_6") (pintype "passive"))
      (node (ref "JP61") (pin "7") (pinfunction "7_7") (pintype "passive"))
      (node (ref "JP61") (pin "8") (pinfunction "8_8") (pintype "passive"))
      (node (ref "JP61") (pin "9") (pinfunction "9_9") (pintype "passive"))
      (node (ref "Q5") (pin "2") (pinfunction "S_2") (pintype "passive"))
      (node (ref "R1") (pin "2") (pinfunction "2_2") (pintype "passive"))
      (node (ref "R11") (pin "2") (pinfunction "2_2") (pintype "passive"))
      (node (ref "R17") (pin "2") (pinfunction "2_2") (pintype "passive"))
      (node (ref "TURN") (pin "1") (pinfunction "O_1") (pintype "passive"))
    )
    (net (code "3") (name "/5VB") (class "Default")
      (node (ref "1-3(5V)1") (pin "1") (pinfunction "1_1") (pintype "passive"))
      (node (ref "5VB") (pin "1") (pinfunction "1_1") (pintype "passive"))
      (node (ref "JP1") (pin "4") (pinfunction "4_4") (pintype "passive"))
      (node (ref "R2") (pin "2") (pinfunction "2_2") (pintype "passive"))
    )
    (net (code "4") (name "/A1") (class "Default")
      (node (ref "3-28") (pin "1") (pinfunction "1_1") (pintype "passive"))
      (node (ref "A1") (pin "1") (pinfunction "1_1") (pintype "passive"))
      (node (ref "JP10") (pin "4") (pinfunction "4_4") (pintype "passive"))
      (node (ref "JP3") (pin "8") (pinfunction "8_8") (pintype "passive"))
    )
    (net (code "5") (name "/A2") (class "Default")
      (node (ref "3-20") (pin "1") (pinfunction "1_1") (pintype "passive"))
      (node (ref "A2") (pin "1") (pinfunction "1_1") (pintype "passive"))
      (node (ref "JP10") (pin "5") (pinfunction "5_5") (pintype "passive"))
      (node (ref "JP3") (pin "7") (pinfunction "7_7") (pintype "passive"))
    )
    (net (code "6") (name "/B1") (class "Default")
      (node (ref "3-26") (pin "1") (pinfunction "1_1") (pintype "passive"))
      (node (ref "B1") (pin "1") (pinfunction "1_1") (pintype "passive"))
      (node (ref "JP16") (pin "12") (pinfunction "12_12") (pintype "passive"))
      (node (ref "JP3") (pin "4") (pinfunction "4_4") (pintype "passive"))
    )
    (net (code "7") (name "/B2") (class "Default")
      (node (ref "3-18") (pin "1") (pinfunction "1_1") (pintype "passive"))
      (node (ref "B2") (pin "1") (pinfunction "1_1") (pintype "passive"))
      (node (ref "JP16") (pin "13") (pinfunction "13_13") (pintype "passive"))
      (node (ref "JP3") (pin "3") (pinfunction "3_3") (pintype "passive"))
    )
    (net (code "8") (name "/B3") (class "Default")
      (node (ref "3-25") (pin "1") (pinfunction "1_1") (pintype "passive"))
      (node (ref "B3") (pin "1") (pinfunction "1_1") (pintype "passive"))
      (node (ref "JP16") (pin "14") (pinfunction "14_14") (pintype "passive"))
      (node (ref "JP3") (pin "2") (pinfunction "2_2") (pintype "passive"))
    )
    (net (code "9") (name "/BCK1UDIM1") (class "Default")
      (node (ref "1-26") (pin "1") (pinfunction "1_1") (pintype "passive"))
      (node (ref "JP1") (pin "8") (pinfunction "8_8") (pintype "passive"))
      (node (ref "R4") (pin "2") (pinfunction "2_2") (pintype "passive"))
      (node (ref "UDIM1-1") (pin "1") (pinfunction "1_1") (pintype "passive"))
    )
    (net (code "10") (name "/BCK1UDIM2") (class "Default")
      (node (ref "11-2") (pin "1") (pinfunction "1_1") (pintype "passive"))
      (node (ref "JP1") (pin "7") (pinfunction "7_7") (pintype "passive"))
      (node (ref "R3") (pin "2") (pinfunction "2_2") (pintype "passive"))
      (node (ref "UDIM1-2") (pin "1") (pinfunction "1_1") (pintype "passive"))
    )
    (net (code "11") (name "/BCK2UDIM1") (class "Default")
      (node (ref "1-25") (pin "1") (pinfunction "1_1") (pintype "passive"))
      (node (ref "JP1") (pin "6") (pinfunction "6_6") (pintype "passive"))
      (node (ref "JP10") (pin "15") (pinfunction "15_15") (pintype "passive"))
      (node (ref "R5") (pin "2") (pinfunction "2_2") (pintype "passive"))
      (node (ref "UDIM2-1") (pin "1") (pinfunction "1_1") (pintype "passive"))
    )
    (net (code "12") (name "/BCK2UDIM2") (class "Default")
      (node (ref "1-1") (pin "1") (pinfunction "1_1") (pintype "passive"))
      (node (ref "JP1") (pin "5") (pinfunction "5_5") (pintype "passive"))
      (node (ref "JP10") (pin "14") (pinfunction "14_14") (pintype "passive"))
      (node (ref "R6") (pin "2") (pinfunction "2_2") (pintype "passive"))
      (node (ref "UDM2-2") (pin "1") (pinfunction "1_1") (pintype "passive"))
    )
    (net (code "13") (name "/DISCHARGE") (class "Default")
      (node (ref "3-19") (pin "1") (pinfunction "1_1") (pintype "passive"))
      (node (ref "JP16") (pin "11") (pinfunction "11_11") (pintype "passive"))
      (node (ref "JP3") (pin "5") (pinfunction "5_5") (pintype "passive"))
      (node (ref "放電") (pin "1") (pinfunction "1_1") (pintype "passive"))
    )
    (net (code "14") (name "/ESP32_HL_BKUP") (class "Default")
      (node (ref "JP16") (pin "6") (pinfunction "6_6") (pintype "passive"))
      (node (ref "Q6") (pin "1") (pinfunction "G_1") (pintype "passive"))
      (node (ref "R18") (pin "1") (pinfunction "1_1") (pintype "passive"))
    )
    (net (code "15") (name "/ESP32_TURN_SYNC") (class "Default")
      (node (ref "JP16") (pin "4") (pinfunction "4_4") (pintype "passive"))
      (node (ref "Q7") (pin "1") (pinfunction "G_1") (pintype "passive"))
      (node (ref "R19") (pin "2") (pinfunction "2_2") (pintype "passive"))
    )
    (net (code "16") (name "/ESP_IG1_SW") (class "Default")
      (node (ref "JP10") (pin "10") (pinfunction "10_10") (pintype "passive"))
      (node (ref "Q3") (pin "1") (pinfunction "G_1") (pintype "passive"))
      (node (ref "R15") (pin "2") (pinfunction "2_2") (pintype "passive"))
    )
    (net (code "17") (name "/ESP_VBU_SW") (class "Default")
      (node (ref "JP10") (pin "11") (pinfunction "11_11") (pintype "passive"))
      (node (ref "Q4") (pin "1") (pinfunction "G_1") (pintype "passive"))
      (node (ref "R16") (pin "2") (pinfunction "2_2") (pintype "passive"))
    )
    (net (code "18") (name "/HL_BKUP") (class "Default")
      (node (ref "2-24") (pin "1") (pinfunction "1_1") (pintype "passive"))
      (node (ref "H/L") (pin "2") (pinfunction "P_2") (pintype "passive"))
      (node (ref "HL_BK") (pin "1") (pinfunction "1_1") (pintype "passive"))
      (node (ref "JP2") (pin "11") (pinfunction "11_11") (pintype "passive"))
      (node (ref "Q6") (pin "3") (pinfunction "D_3") (pintype "passive"))
    )
    (net (code "19") (name "/IG1") (class "Default")
      (node (ref "IG1") (pin "2") (pinfunction "P_2") (pintype "passive"))
      (node (ref "JP63") (pin "2") (pinfunction "2_2") (pintype "passive"))
      (node (ref "Q1") (pin "3") (pinfunction "D_3") (pintype "passive"))
      (node (ref "R12") (pin "2") (pinfunction "2_2") (pintype "passive"))
    )
    (net (code "20") (name "/INSIDE_THM") (class "Default")
      (node (ref "2-35") (pin "1") (pinfunction "1_1") (pintype "passive"))
      (node (ref "JP2") (pin "16") (pinfunction "16_16") (pintype "passive"))
      (node (ref "U$1") (pin "P$6") (pinfunction "O_A_P$6") (pintype "bidirectional"))
      (node (ref "内温") (pin "1") (pinfunction "1_1") (pintype "passive"))
    )
    (net (code "21") (name "/LED_THM1") (class "Default")
      (node (ref "2-26") (pin "1") (pinfunction "1_1") (pintype "passive"))
      (node (ref "JP2") (pin "15") (pinfunction "15_15") (pintype "passive"))
      (node (ref "LED温1") (pin "1") (pinfunction "1_1") (pintype "passive"))
      (node (ref "U$1") (pin "P$7") (pinfunction "O_B_P$7") (pintype "bidirectional"))
    )
    (net (code "22") (name "/LED_THM2") (class "Default")
      (node (ref "2-34") (pin "1") (pinfunction "1_1") (pintype "passive"))
      (node (ref "JP2") (pin "14") (pinfunction "14_14") (pintype "passive"))
      (node (ref "LED温2") (pin "1") (pinfunction "1_1") (pintype "passive"))
      (node (ref "U$1") (pin "P$8") (pinfunction "O_C_P$8") (pintype "bidirectional"))
    )
    (net (code "23") (name "/LED_THM3") (class "Default")
      (node (ref "2-25") (pin "1") (pinfunction "1_1") (pintype "passive"))
      (node (ref "JP2") (pin "13") (pinfunction "13_13") (pintype "passive"))
      (node (ref "LED温3") (pin "1") (pinfunction "1_1") (pintype "passive"))
      (node (ref "U$1") (pin "P$9") (pinfunction "O_D_P$9") (pintype "bidirectional"))
    )
    (net (code "24") (name "/LIN_TX") (class "Default")
      (node (ref "2-18") (pin "1") (pinfunction "1_1") (pintype "passive"))
      (node (ref "2-36") (pin "1") (pinfunction "1_1") (pintype "passive"))
      (node (ref "JP10") (pin "7") (pinfunction "7_7") (pintype "passive"))
      (node (ref "JP2") (pin "18") (pinfunction "18_18") (pintype "passive"))
    )
    (net (code "25") (name "/SPI_CLK") (class "Default")
      (node (ref "1-32") (pin "1") (pinfunction "1_1") (pintype "passive"))
      (node (ref "CLK") (pin "1") (pinfunction "1_1") (pintype "passive"))
      (node (ref "JP1") (pin "20") (pinfunction "20_20") (pintype "passive"))
      (node (ref "JP16") (pin "5") (pinfunction "5_5") (pintype "passive"))
    )
    (net (code "26") (name "/SPI_CS_BK1") (class "Default")
      (node (ref "1-30") (pin "1") (pinfunction "1_1") (pintype "passive"))
      (node (ref "CS_BK1") (pin "1") (pinfunction "1_1") (pintype "passive"))
      (node (ref "D1") (pin "C") (pinfunction "C_C") (pintype "passive"))
      (node (ref "JP1") (pin "16") (pinfunction "16_16") (pintype "passive"))
    )
    (net (code "27") (name "/SPI_CS_BK2") (class "Default")
      (node (ref "1-22") (pin "1") (pinfunction "1_1") (pintype "passive"))
      (node (ref "CS_BK2") (pin "1") (pinfunction "1_1") (pintype "passive"))
      (node (ref "D2") (pin "C") (pinfunction "C_C") (pintype "passive"))
      (node (ref "JP1") (pin "15") (pinfunction "15_15") (pintype "passive"))
    )
    (net (code "28") (name "/SPI_CS_BST") (class "Default")
      (node (ref "1-29") (pin "1") (pinfunction "1_1") (pintype "passive"))
      (node (ref "CS_BST") (pin "1") (pinfunction "1_1") (pintype "passive"))
      (node (ref "D3") (pin "C") (pinfunction "C_C") (pintype "passive"))
      (node (ref "JP1") (pin "14") (pinfunction "14_14") (pintype "passive"))
    )
    (net (code "29") (name "/SPI_MOSI") (class "Default")
      (node (ref "1-31") (pin "1") (pinfunction "1_1") (pintype "passive"))
      (node (ref "JP1") (pin "18") (pinfunction "18_18") (pintype "passive"))
      (node (ref "JP16") (pin "3") (pinfunction "3_3") (pintype "passive"))
      (node (ref "MOSI") (pin "1") (pinfunction "1_1") (pintype "passive"))
    )
    (net (code "30") (name "/TURN_SYNC") (class "Default")
      (node (ref "2-33") (pin "1") (pinfunction "1_1") (pintype "passive"))
      (node (ref "JP2") (pin "12") (pinfunction "12_12") (pintype "passive"))
      (node (ref "Q5") (pin "3") (pinfunction "D_3") (pintype "passive"))
      (node (ref "TURN") (pin "2") (pinfunction "P_2") (pintype "passive"))
      (node (ref "TURN_S") (pin "1") (pinfunction "1_1") (pintype "passive"))
    )
    (net (code "31") (name "/UARTTX") (class "Default")
      (node (ref "1-23") (pin "1") (pinfunction "1_1") (pintype "passive"))
      (node (ref "JP1") (pin "17") (pinfunction "17_17") (pintype "passive"))
      (node (ref "JP10") (pin "6") (pinfunction "6_6") (pintype "passive"))
      (node (ref "U_TX") (pin "1") (pinfunction "1_1") (pintype "passive"))
    )
    (net (code "32") (name "/USB_5V") (class "Default")
      (node (ref "JP14") (pin "1") (pinfunction "1_1") (pintype "passive"))
      (node (ref "JP15") (pin "1") (pinfunction "1_1") (pintype "passive"))
      (node (ref "U$1") (pin "P$1") (pinfunction "VDD_P$1") (pintype "bidirectional"))
    )
    (net (code "33") (name "/VBST") (class "Default")
      (node (ref "1-2(GND)1") (pin "1") (pinfunction "1_1") (pintype "passive"))
      (node (ref "JP1") (pin "1") (pinfunction "1_1") (pintype "passive"))
      (node (ref "R10") (pin "2") (pinfunction "2_2") (pintype "passive"))
      (node (ref "R9") (pin "2") (pinfunction "2_2") (pintype "passive"))
      (node (ref "VBST") (pin "1") (pinfunction "1_1") (pintype "passive"))
    )
    (net (code "34") (name "GND") (class "Default")
      (node (ref "BUCK1_1") (pin "C") (pinfunction "C_C") (pintype "passive"))
      (node (ref "BUCK1_2") (pin "C") (pinfunction "C_C") (pintype "passive"))
      (node (ref "BUCK2_1") (pin "C") (pinfunction "C_C") (pintype "passive"))
      (node (ref "BUCK_2_2") (pin "C") (pinfunction "C_C") (pintype "passive"))
      (node (ref "H/L") (pin "1") (pinfunction "O_1") (pintype "passive"))
      (node (ref "JP10") (pin "2") (pinfunction "2_2") (pintype "passive"))
      (node (ref "JP11") (pin "2") (pinfunction "2_2") (pintype "passive"))
      (node (ref "JP12") (pin "2") (pinfunction "2_2") (pintype "passive"))
      (node (ref "JP14") (pin "2") (pinfunction "2_2") (pintype "passive"))
      (node (ref "JP15") (pin "2") (pinfunction "2_2") (pintype "passive"))
      (node (ref "JP16") (pin "2") (pinfunction "2_2") (pintype "passive"))
      (node (ref "JP59") (pin "1") (pinfunction "1_1") (pintype "passive"))
      (node (ref "JP59") (pin "10") (pinfunction "10_10") (pintype "passive"))
      (node (ref "JP59") (pin "11") (pinfunction "11_11") (pintype "passive"))
      (node (ref "JP59") (pin "12") (pinfunction "12_12") (pintype "passive"))
      (node (ref "JP59") (pin "13") (pinfunction "13_13") (pintype "passive"))
      (node (ref "JP59") (pin "14") (pinfunction "14_14") (pintype "passive"))
      (node (ref "JP59") (pin "15") (pinfunction "15_15") (pintype "passive"))
      (node (ref "JP59") (pin "16") (pinfunction "16_16") (pintype "passive"))
      (node (ref "JP59") (pin "2") (pinfunction "2_2") (pintype "passive"))
      (node (ref "JP59") (pin "3") (pinfunction "3_3") (pintype "passive"))
      (node (ref "JP59") (pin "4") (pinfunction "4_4") (pintype "passive"))
      (node (ref "JP59") (pin "5") (pinfunction "5_5") (pintype "passive"))
      (node (ref "JP59") (pin "6") (pinfunction "6_6") (pintype "passive"))
      (node (ref "JP59") (pin "7") (pinfunction "7_7") (pintype "passive"))
      (node (ref "JP59") (pin "8") (pinfunction "8_8") (pintype "passive"))
      (node (ref "JP59") (pin "9") (pinfunction "9_9") (pintype "passive"))
      (node (ref "JP63") (pin "1") (pinfunction "1_1") (pintype "passive"))
      (node (ref "LED_5VA") (pin "C") (pinfunction "C_C") (pintype "passive"))
      (node (ref "LED_5VB") (pin "C") (pinfunction "C_C") (pintype "passive"))
      (node (ref "LED_BOOST") (pin "C") (pinfunction "C_C") (pintype "passive"))
      (node (ref "LED_IG1") (pin "C") (pinfunction "C_C") (pintype "passive"))
      (node (ref "Q3") (pin "2") (pinfunction "S_2") (pintype "passive"))
      (node (ref "Q4") (pin "2") (pinfunction "S_2") (pintype "passive"))
      (node (ref "Q6") (pin "2") (pinfunction "S_2") (pintype "passive"))
      (node (ref "Q7") (pin "2") (pinfunction "S_2") (pintype "passive"))
      (node (ref "R15") (pin "1") (pinfunction "1_1") (pintype "passive"))
      (node (ref "R16") (pin "1") (pinfunction "1_1") (pintype "passive"))
      (node (ref "R18") (pin "2") (pinfunction "2_2") (pintype "passive"))
      (node (ref "R19") (pin "1") (pinfunction "1_1") (pintype "passive"))
      (node (ref "U$1") (pin "P$10") (pinfunction "VSS_P$10") (pintype "bidirectional"))
      (node (ref "電源") (pin "1") (pinfunction "1_1") (pintype "passive"))
    )
    (net (code "35") (name "Net-(1-1(+B)1-Pad1)") (class "Default")
      (node (ref "1-1(+B)1") (pin "1") (pinfunction "1_1") (pintype "passive"))
      (node (ref "1-2") (pin "1") (pinfunction "1_1") (pintype "passive"))
      (node (ref "JP1") (pin "2") (pinfunction "2_2") (pintype "passive"))
    )
    (net (code "36") (name "Net-(1-3-Pad1)") (class "Default")
      (node (ref "1-3") (pin "1") (pinfunction "1_1") (pintype "passive"))
      (node (ref "1-9") (pin "1") (pinfunction "1_1") (pintype "passive"))
      (node (ref "JP1") (pin "9") (pinfunction "9_9") (pintype "passive"))
    )
    (net (code "37") (name "Net-(1-21-Pad1)") (class "Default")
      (node (ref "1-21") (pin "1") (pinfunction "1_1") (pintype "passive"))
      (node (ref "JP1") (pin "13") (pinfunction "13_13") (pintype "passive"))
      (node (ref "U_RX") (pin "1") (pinfunction "1_1") (pintype "passive"))
    )
    (net (code "38") (name "Net-(1-24-Pad1)") (class "Default")
      (node (ref "1-24") (pin "1") (pinfunction "1_1") (pintype "passive"))
      (node (ref "JP1") (pin "19") (pinfunction "19_19") (pintype "passive"))
      (node (ref "MISO") (pin "1") (pinfunction "1_1") (pintype "passive"))
    )
    (net (code "39") (name "Net-(1-27-Pad1)") (class "Default")
      (node (ref "1-27") (pin "1") (pinfunction "1_1") (pintype "passive"))
      (node (ref "DEBG1") (pin "1") (pinfunction "1_1") (pintype "passive"))
      (node (ref "JP1") (pin "10") (pinfunction "10_10") (pintype "passive"))
    )
    (net (code "40") (name "Net-(1-28-Pad1)") (class "Default")
      (node (ref "1-28") (pin "1") (pinfunction "1_1") (pintype "passive"))
      (node (ref "BST_E") (pin "1") (pinfunction "1_1") (pintype "passive"))
      (node (ref "JP1") (pin "12") (pinfunction "12_12") (pintype "passive"))
    )
    (net (code "41") (name "Net-(2-1-Pad1)") (class "Default")
      (node (ref "2-1") (pin "1") (pinfunction "1_1") (pintype "passive"))
      (node (ref "2-19") (pin "1") (pinfunction "1_1") (pintype "passive"))
      (node (ref "JP2") (pin "1") (pinfunction "1_1") (pintype "passive"))
    )
    (net (code "42") (name "Net-(2-10-Pad1)") (class "Default")
      (node (ref "2-10") (pin "1") (pinfunction "1_1") (pintype "passive"))
      (node (ref "2-32") (pin "1") (pinfunction "1_1") (pintype "passive"))
      (node (ref "JP2") (pin "10") (pinfunction "10_10") (pintype "passive"))
    )
    (net (code "43") (name "Net-(2-17-Pad1)") (class "Default")
      (node (ref "2-17") (pin "1") (pinfunction "1_1") (pintype "passive"))
      (node (ref "2-27") (pin "1") (pinfunction "1_1") (pintype "passive"))
      (node (ref "JP2") (pin "17") (pinfunction "17_17") (pintype "passive"))
    )
    (net (code "44") (name "Net-(2-20-Pad1)") (class "Default")
      (node (ref "2-20") (pin "1") (pinfunction "1_1") (pintype "passive"))
      (node (ref "AD_B2") (pin "1") (pinfunction "1_1") (pintype "passive"))
      (node (ref "JP2") (pin "3") (pinfunction "3_3") (pintype "passive"))
    )
    (net (code "45") (name "Net-(2-21-Pad1)") (class "Default")
      (node (ref "2-21") (pin "1") (pinfunction "1_1") (pintype "passive"))
      (node (ref "2-5") (pin "1") (pinfunction "1_1") (pintype "passive"))
      (node (ref "JP2") (pin "5") (pinfunction "5_5") (pintype "passive"))
    )
    (net (code "46") (name "Net-(2-22-Pad1)") (class "Default")
      (node (ref "2-22") (pin "1") (pinfunction "1_1") (pintype "passive"))
      (node (ref "AD_A2") (pin "1") (pinfunction "1_1") (pintype "passive"))
      (node (ref "JP2") (pin "7") (pinfunction "7_7") (pintype "passive"))
    )
    (net (code "47") (name "Net-(2-23-Pad1)") (class "Default")
      (node (ref "2-23") (pin "1") (pinfunction "1_1") (pintype "passive"))
      (node (ref "2-9") (pin "1") (pinfunction "1_1") (pintype "passive"))
      (node (ref "JP2") (pin "9") (pinfunction "9_9") (pintype "passive"))
    )
    (net (code "48") (name "Net-(2-28-Pad1)") (class "Default")
      (node (ref "2-28") (pin "1") (pinfunction "1_1") (pintype "passive"))
      (node (ref "AD_B3") (pin "1") (pinfunction "1_1") (pintype "passive"))
      (node (ref "JP2") (pin "2") (pinfunction "2_2") (pintype "passive"))
    )
    (net (code "49") (name "Net-(2-29-Pad1)") (class "Default")
      (node (ref "2-29") (pin "1") (pinfunction "1_1") (pintype "passive"))
      (node (ref "AD_B1") (pin "1") (pinfunction "1_1") (pintype "passive"))
      (node (ref "JP2") (pin "4") (pinfunction "4_4") (pintype "passive"))
    )
    (net (code "50") (name "Net-(2-30-Pad1)") (class "Default")
      (node (ref "2-30") (pin "1") (pinfunction "1_1") (pintype "passive"))
      (node (ref "2-6") (pin "1") (pinfunction "1_1") (pintype "passive"))
      (node (ref "JP2") (pin "6") (pinfunction "6_6") (pintype "passive"))
    )
    (net (code "51") (name "Net-(2-31-Pad1)") (class "Default")
      (node (ref "2-31") (pin "1") (pinfunction "1_1") (pintype "passive"))
      (node (ref "AD_A1") (pin "1") (pinfunction "1_1") (pintype "passive"))
      (node (ref "JP2") (pin "8") (pinfunction "8_8") (pintype "passive"))
    )
    (net (code "52") (name "Net-(3-1-Pad1)") (class "Default")
      (node (ref "3-1") (pin "1") (pinfunction "1_1") (pintype "passive"))
      (node (ref "3-17") (pin "1") (pinfunction "1_1") (pintype "passive"))
      (node (ref "JP3") (pin "1") (pinfunction "1_1") (pintype "passive"))
    )
    (net (code "53") (name "Net-(3-10-Pad1)") (class "Default")
      (node (ref "3-10") (pin "1") (pinfunction "1_1") (pintype "passive"))
      (node (ref "3-29") (pin "1") (pinfunction "1_1") (pintype "passive"))
      (node (ref "JP3") (pin "10") (pinfunction "10_10") (pintype "passive"))
    )
    (net (code "54") (name "Net-(3-11-Pad1)") (class "Default")
      (node (ref "3-11") (pin "1") (pinfunction "1_1") (pintype "passive"))
      (node (ref "3-22") (pin "1") (pinfunction "1_1") (pintype "passive"))
      (node (ref "JP3") (pin "11") (pinfunction "11_11") (pintype "passive"))
    )
    (net (code "55") (name "Net-(3-12-Pad1)") (class "Default")
      (node (ref "3-12") (pin "1") (pinfunction "1_1") (pintype "passive"))
      (node (ref "3-30") (pin "1") (pinfunction "1_1") (pintype "passive"))
      (node (ref "JP3") (pin "12") (pinfunction "12_12") (pintype "passive"))
    )
    (net (code "56") (name "Net-(3-13-Pad1)") (class "Default")
      (node (ref "3-13") (pin "1") (pinfunction "1_1") (pintype "passive"))
      (node (ref "3-23") (pin "1") (pinfunction "1_1") (pintype "passive"))
      (node (ref "JP3") (pin "13") (pinfunction "13_13") (pintype "passive"))
    )
    (net (code "57") (name "Net-(3-14-Pad1)") (class "Default")
      (node (ref "3-14") (pin "1") (pinfunction "1_1") (pintype "passive"))
      (node (ref "3-31") (pin "1") (pinfunction "1_1") (pintype "passive"))
      (node (ref "JP3") (pin "14") (pinfunction "14_14") (pintype "passive"))
    )
    (net (code "58") (name "Net-(3-15-Pad1)") (class "Default")
      (node (ref "3-15") (pin "1") (pinfunction "1_1") (pintype "passive"))
      (node (ref "3-24") (pin "1") (pinfunction "1_1") (pintype "passive"))
      (node (ref "JP3") (pin "15") (pinfunction "15_15") (pintype "passive"))
    )
    (net (code "59") (name "Net-(3-16-Pad1)") (class "Default")
      (node (ref "3-16") (pin "1") (pinfunction "1_1") (pintype "passive"))
      (node (ref "3-32") (pin "1") (pinfunction "1_1") (pintype "passive"))
      (node (ref "JP3") (pin "16") (pinfunction "16_16") (pintype "passive"))
    )
    (net (code "60") (name "Net-(3-21-Pad1)") (class "Default")
      (node (ref "3-21") (pin "1") (pinfunction "1_1") (pintype "passive"))
      (node (ref "3-9") (pin "1") (pinfunction "1_1") (pintype "passive"))
      (node (ref "JP3") (pin "9") (pinfunction "9_9") (pintype "passive"))
    )
    (net (code "61") (name "Net-(3-27-Pad1)") (class "Default")
      (node (ref "3-27") (pin "1") (pinfunction "1_1") (pintype "passive"))
      (node (ref "3-6") (pin "1") (pinfunction "1_1") (pintype "passive"))
      (node (ref "JP3") (pin "6") (pinfunction "6_6") (pintype "passive"))
    )
    (net (code "62") (name "Net-(11-4-Pad1)") (class "Default")
      (node (ref "11-4") (pin "1") (pinfunction "1_1") (pintype "passive"))
      (node (ref "BST_S") (pin "1") (pinfunction "1_1") (pintype "passive"))
      (node (ref "JP1") (pin "11") (pinfunction "11_11") (pintype "passive"))
    )
    (net (code "63") (name "Net-(BUCK1_1-PadA)") (class "Default")
      (node (ref "BUCK1_1") (pin "A") (pinfunction "A_A") (pintype "passive"))
      (node (ref "R4") (pin "1") (pinfunction "1_1") (pintype "passive"))
    )
    (net (code "64") (name "Net-(BUCK1_2-PadA)") (class "Default")
      (node (ref "BUCK1_2") (pin "A") (pinfunction "A_A") (pintype "passive"))
      (node (ref "R3") (pin "1") (pinfunction "1_1") (pintype "passive"))
    )
    (net (code "65") (name "Net-(BUCK2_1-PadA)") (class "Default")
      (node (ref "BUCK2_1") (pin "A") (pinfunction "A_A") (pintype "passive"))
      (node (ref "R5") (pin "1") (pinfunction "1_1") (pintype "passive"))
    )
    (net (code "66") (name "Net-(BUCK_2_2-PadA)") (class "Default")
      (node (ref "BUCK_2_2") (pin "A") (pinfunction "A_A") (pintype "passive"))
      (node (ref "R6") (pin "1") (pinfunction "1_1") (pintype "passive"))
    )
    (net (code "67") (name "Net-(D1-PadA)") (class "Default")
      (node (ref "D1") (pin "A") (pinfunction "A_A") (pintype "passive"))
      (node (ref "D2") (pin "A") (pinfunction "A_A") (pintype "passive"))
      (node (ref "D3") (pin "A") (pinfunction "A_A") (pintype "passive"))
      (node (ref "JP10") (pin "3") (pinfunction "3_3") (pintype "passive"))
      (node (ref "R11") (pin "1") (pinfunction "1_1") (pintype "passive"))
    )
    (net (code "68") (name "Net-(JP4-Pad1)") (class "Default")
      (node (ref "JP4") (pin "1") (pinfunction "1_1") (pintype "passive"))
      (node (ref "JP4") (pin "2") (pinfunction "2_2") (pintype "passive"))
      (node (ref "JP4") (pin "3") (pinfunction "3_3") (pintype "passive"))
    )
    (net (code "69") (name "Net-(JP5-Pad1)") (class "Default")
      (node (ref "JP5") (pin "1") (pinfunction "1_1") (pintype "passive"))
      (node (ref "JP5") (pin "2") (pinfunction "2_2") (pintype "passive"))
      (node (ref "JP5") (pin "3") (pinfunction "3_3") (pintype "passive"))
    )
    (net (code "70") (name "Net-(JP6-Pad1)") (class "Default")
      (node (ref "JP6") (pin "1") (pinfunction "1_1") (pintype "passive"))
      (node (ref "JP6") (pin "2") (pinfunction "2_2") (pintype "passive"))
      (node (ref "JP6") (pin "3") (pinfunction "3_3") (pintype "passive"))
    )
    (net (code "71") (name "Net-(JP7-Pad1)") (class "Default")
      (node (ref "JP7") (pin "1") (pinfunction "1_1") (pintype "passive"))
      (node (ref "JP7") (pin "2") (pinfunction "2_2") (pintype "passive"))
      (node (ref "JP7") (pin "3") (pinfunction "3_3") (pintype "passive"))
    )
    (net (code "72") (name "Net-(JP8-Pad1)") (class "Default")
      (node (ref "JP8") (pin "1") (pinfunction "1_1") (pintype "passive"))
      (node (ref "JP8") (pin "2") (pinfunction "2_2") (pintype "passive"))
      (node (ref "JP8") (pin "3") (pinfunction "3_3") (pintype "passive"))
    )
    (net (code "73") (name "Net-(JP9-Pad1)") (class "Default")
      (node (ref "JP9") (pin "1") (pinfunction "1_1") (pintype "passive"))
      (node (ref "JP9") (pin "2") (pinfunction "2_2") (pintype "passive"))
      (node (ref "JP9") (pin "3") (pinfunction "3_3") (pintype "passive"))
    )
    (net (code "74") (name "Net-(JP11-Pad1)") (class "Default")
      (node (ref "JP11") (pin "1") (pinfunction "1_1") (pintype "passive"))
      (node (ref "JP12") (pin "1") (pinfunction "1_1") (pintype "passive"))
    )
    (net (code "75") (name "Net-(JP11-Pad3)") (class "Default")
      (node (ref "JP11") (pin "3") (pinfunction "3_3") (pintype "passive"))
      (node (ref "JP12") (pin "3") (pinfunction "3_3") (pintype "passive"))
    )
    (net (code "76") (name "Net-(JP11-Pad4)") (class "Default")
      (node (ref "JP11") (pin "4") (pinfunction "4_4") (pintype "passive"))
      (node (ref "JP12") (pin "4") (pinfunction "4_4") (pintype "passive"))
    )
    (net (code "77") (name "Net-(JP11-Pad5)") (class "Default")
      (node (ref "JP11") (pin "5") (pinfunction "5_5") (pintype "passive"))
      (node (ref "JP12") (pin "5") (pinfunction "5_5") (pintype "passive"))
    )
    (net (code "78") (name "Net-(JP11-Pad6)") (class "Default")
      (node (ref "JP11") (pin "6") (pinfunction "6_6") (pintype "passive"))
      (node (ref "JP12") (pin "6") (pinfunction "6_6") (pintype "passive"))
    )
    (net (code "79") (name "Net-(JP11-Pad7)") (class "Default")
      (node (ref "JP11") (pin "7") (pinfunction "7_7") (pintype "passive"))
      (node (ref "JP12") (pin "7") (pinfunction "7_7") (pintype "passive"))
    )
    (net (code "80") (name "Net-(JP11-Pad8)") (class "Default")
      (node (ref "JP11") (pin "8") (pinfunction "8_8") (pintype "passive"))
      (node (ref "JP12") (pin "8") (pinfunction "8_8") (pintype "passive"))
    )
    (net (code "81") (name "Net-(JP11-Pad9)") (class "Default")
      (node (ref "JP11") (pin "9") (pinfunction "9_9") (pintype "passive"))
      (node (ref "JP12") (pin "9") (pinfunction "9_9") (pintype "passive"))
    )
    (net (code "82") (name "Net-(JP11-Pad10)") (class "Default")
      (node (ref "JP11") (pin "10") (pinfunction "10_10") (pintype "passive"))
      (node (ref "JP12") (pin "10") (pinfunction "10_10") (pintype "passive"))
    )
    (net (code "83") (name "Net-(JP11-Pad11)") (class "Default")
      (node (ref "JP11") (pin "11") (pinfunction "11_11") (pintype "passive"))
      (node (ref "JP12") (pin "11") (pinfunction "11_11") (pintype "passive"))
    )
    (net (code "84") (name "Net-(JP11-Pad12)") (class "Default")
      (node (ref "JP11") (pin "12") (pinfunction "12_12") (pintype "passive"))
      (node (ref "JP12") (pin "12") (pinfunction "12_12") (pintype "passive"))
    )
    (net (code "85") (name "Net-(JP11-Pad13)") (class "Default")
      (node (ref "JP11") (pin "13") (pinfunction "13_13") (pintype "passive"))
      (node (ref "JP12") (pin "13") (pinfunction "13_13") (pintype "passive"))
    )
    (net (code "86") (name "Net-(JP11-Pad14)") (class "Default")
      (node (ref "JP11") (pin "14") (pinfunction "14_14") (pintype "passive"))
      (node (ref "JP12") (pin "14") (pinfunction "14_14") (pintype "passive"))
    )
    (net (code "87") (name "Net-(JP11-Pad15)") (class "Default")
      (node (ref "JP11") (pin "15") (pinfunction "15_15") (pintype "passive"))
      (node (ref "JP12") (pin "15") (pinfunction "15_15") (pintype "passive"))
    )
    (net (code "88") (name "Net-(JP13-Pad1)") (class "Default")
      (node (ref "JP13") (pin "1") (pinfunction "1_1") (pintype "passive"))
      (node (ref "JP13") (pin "2") (pinfunction "2_2") (pintype "passive"))
      (node (ref "JP13") (pin "3") (pinfunction "3_3") (pintype "passive"))
    )
    (net (code "89") (name "Net-(JP14-Pad3)") (class "Default")
      (node (ref "JP14") (pin "3") (pinfunction "3_3") (pintype "passive"))
      (node (ref "JP15") (pin "3") (pinfunction "3_3") (pintype "passive"))
    )
    (net (code "90") (name "Net-(JP14-Pad4)") (class "Default")
      (node (ref "JP14") (pin "4") (pinfunction "4_4") (pintype "passive"))
      (node (ref "JP15") (pin "4") (pinfunction "4_4") (pintype "passive"))
    )
    (net (code "91") (name "Net-(JP14-Pad5)") (class "Default")
      (node (ref "JP14") (pin "5") (pinfunction "5_5") (pintype "passive"))
      (node (ref "JP15") (pin "5") (pinfunction "5_5") (pintype "passive"))
    )
    (net (code "92") (name "Net-(JP14-Pad6)") (class "Default")
      (node (ref "JP14") (pin "6") (pinfunction "6_6") (pintype "passive"))
      (node (ref "JP15") (pin "6") (pinfunction "6_6") (pintype "passive"))
    )
    (net (code "93") (name "Net-(JP14-Pad7)") (class "Default")
      (node (ref "JP14") (pin "7") (pinfunction "7_7") (pintype "passive"))
      (node (ref "JP15") (pin "7") (pinfunction "7_7") (pintype "passive"))
    )
    (net (code "94") (name "Net-(JP14-Pad8)") (class "Default")
      (node (ref "JP14") (pin "8") (pinfunction "8_8") (pintype "passive"))
      (node (ref "JP15") (pin "8") (pinfunction "8_8") (pintype "passive"))
    )
    (net (code "95") (name "Net-(JP14-Pad9)") (class "Default")
      (node (ref "JP14") (pin "9") (pinfunction "9_9") (pintype "passive"))
      (node (ref "JP15") (pin "9") (pinfunction "9_9") (pintype "passive"))
    )
    (net (code "96") (name "Net-(JP14-Pad10)") (class "Default")
      (node (ref "JP14") (pin "10") (pinfunction "10_10") (pintype "passive"))
      (node (ref "JP15") (pin "10") (pinfunction "10_10") (pintype "passive"))
    )
    (net (code "97") (name "Net-(JP14-Pad11)") (class "Default")
      (node (ref "JP14") (pin "11") (pinfunction "11_11") (pintype "passive"))
      (node (ref "JP15") (pin "11") (pinfunction "11_11") (pintype "passive"))
    )
    (net (code "98") (name "Net-(JP14-Pad12)") (class "Default")
      (node (ref "JP14") (pin "12") (pinfunction "12_12") (pintype "passive"))
      (node (ref "JP15") (pin "12") (pinfunction "12_12") (pintype "passive"))
    )
    (net (code "99") (name "Net-(JP14-Pad13)") (class "Default")
      (node (ref "JP14") (pin "13") (pinfunction "13_13") (pintype "passive"))
      (node (ref "JP15") (pin "13") (pinfunction "13_13") (pintype "passive"))
    )
    (net (code "100") (name "Net-(JP14-Pad14)") (class "Default")
      (node (ref "JP14") (pin "14") (pinfunction "14_14") (pintype "passive"))
      (node (ref "JP15") (pin "14") (pinfunction "14_14") (pintype "passive"))
    )
    (net (code "101") (name "Net-(JP14-Pad15)") (class "Default")
      (node (ref "JP14") (pin "15") (pinfunction "15_15") (pintype "passive"))
      (node (ref "JP15") (pin "15") (pinfunction "15_15") (pintype "passive"))
    )
    (net (code "102") (name "Net-(JP17-Pad1)") (class "Default")
      (node (ref "JP17") (pin "1") (pinfunction "1_1") (pintype "passive"))
      (node (ref "JP17") (pin "2") (pinfunction "2_2") (pintype "passive"))
      (node (ref "JP17") (pin "3") (pinfunction "3_3") (pintype "passive"))
    )
    (net (code "103") (name "Net-(JP18-Pad1)") (class "Default")
      (node (ref "JP18") (pin "1") (pinfunction "1_1") (pintype "passive"))
      (node (ref "JP18") (pin "2") (pinfunction "2_2") (pintype "passive"))
      (node (ref "JP18") (pin "3") (pinfunction "3_3") (pintype "passive"))
    )
    (net (code "104") (name "Net-(JP19-Pad1)") (class "Default")
      (node (ref "JP19") (pin "1") (pinfunction "1_1") (pintype "passive"))
      (node (ref "JP19") (pin "2") (pinfunction "2_2") (pintype "passive"))
      (node (ref "JP19") (pin "3") (pinfunction "3_3") (pintype "passive"))
    )
    (net (code "105") (name "Net-(JP20-Pad1)") (class "Default")
      (node (ref "JP20") (pin "1") (pinfunction "1_1") (pintype "passive"))
      (node (ref "JP20") (pin "2") (pinfunction "2_2") (pintype "passive"))
      (node (ref "JP20") (pin "3") (pinfunction "3_3") (pintype "passive"))
    )
    (net (code "106") (name "Net-(JP21-Pad1)") (class "Default")
      (node (ref "JP21") (pin "1") (pinfunction "1_1") (pintype "passive"))
      (node (ref "JP21") (pin "2") (pinfunction "2_2") (pintype "passive"))
      (node (ref "JP21") (pin "3") (pinfunction "3_3") (pintype "passive"))
    )
    (net (code "107") (name "Net-(JP22-Pad1)") (class "Default")
      (node (ref "JP22") (pin "1") (pinfunction "1_1") (pintype "passive"))
      (node (ref "JP22") (pin "2") (pinfunction "2_2") (pintype "passive"))
      (node (ref "JP22") (pin "3") (pinfunction "3_3") (pintype "passive"))
    )
    (net (code "108") (name "Net-(JP23-Pad1)") (class "Default")
      (node (ref "JP23") (pin "1") (pinfunction "1_1") (pintype "passive"))
      (node (ref "JP23") (pin "2") (pinfunction "2_2") (pintype "passive"))
      (node (ref "JP23") (pin "3") (pinfunction "3_3") (pintype "passive"))
    )
    (net (code "109") (name "Net-(JP24-Pad1)") (class "Default")
      (node (ref "JP24") (pin "1") (pinfunction "1_1") (pintype "passive"))
      (node (ref "JP24") (pin "2") (pinfunction "2_2") (pintype "passive"))
      (node (ref "JP24") (pin "3") (pinfunction "3_3") (pintype "passive"))
    )
    (net (code "110") (name "Net-(JP25-Pad1)") (class "Default")
      (node (ref "JP25") (pin "1") (pinfunction "1_1") (pintype "passive"))
      (node (ref "JP25") (pin "2") (pinfunction "2_2") (pintype "passive"))
      (node (ref "JP25") (pin "3") (pinfunction "3_3") (pintype "passive"))
    )
    (net (code "111") (name "Net-(JP26-Pad1)") (class "Default")
      (node (ref "JP26") (pin "1") (pinfunction "1_1") (pintype "passive"))
      (node (ref "JP26") (pin "2") (pinfunction "2_2") (pintype "passive"))
      (node (ref "JP26") (pin "3") (pinfunction "3_3") (pintype "passive"))
    )
    (net (code "112") (name "Net-(JP27-Pad1)") (class "Default")
      (node (ref "JP27") (pin "1") (pinfunction "1_1") (pintype "passive"))
      (node (ref "JP27") (pin "2") (pinfunction "2_2") (pintype "passive"))
      (node (ref "JP27") (pin "3") (pinfunction "3_3") (pintype "passive"))
    )
    (net (code "113") (name "Net-(JP28-Pad1)") (class "Default")
      (node (ref "JP28") (pin "1") (pinfunction "1_1") (pintype "passive"))
      (node (ref "JP28") (pin "2") (pinfunction "2_2") (pintype "passive"))
      (node (ref "JP28") (pin "3") (pinfunction "3_3") (pintype "passive"))
    )
    (net (code "114") (name "Net-(JP29-Pad1)") (class "Default")
      (node (ref "JP29") (pin "1") (pinfunction "1_1") (pintype "passive"))
      (node (ref "JP29") (pin "2") (pinfunction "2_2") (pintype "passive"))
      (node (ref "JP29") (pin "3") (pinfunction "3_3") (pintype "passive"))
    )
    (net (code "115") (name "Net-(JP30-Pad1)") (class "Default")
      (node (ref "JP30") (pin "1") (pinfunction "1_1") (pintype "passive"))
      (node (ref "JP30") (pin "2") (pinfunction "2_2") (pintype "passive"))
      (node (ref "JP30") (pin "3") (pinfunction "3_3") (pintype "passive"))
    )
    (net (code "116") (name "Net-(JP31-Pad1)") (class "Default")
      (node (ref "JP31") (pin "1") (pinfunction "1_1") (pintype "passive"))
      (node (ref "JP31") (pin "2") (pinfunction "2_2") (pintype "passive"))
      (node (ref "JP31") (pin "3") (pinfunction "3_3") (pintype "passive"))
    )
    (net (code "117") (name "Net-(JP32-Pad1)") (class "Default")
      (node (ref "JP32") (pin "1") (pinfunction "1_1") (pintype "passive"))
      (node (ref "JP32") (pin "2") (pinfunction "2_2") (pintype "passive"))
      (node (ref "JP32") (pin "3") (pinfunction "3_3") (pintype "passive"))
    )
    (net (code "118") (name "Net-(JP33-Pad1)") (class "Default")
      (node (ref "JP33") (pin "1") (pinfunction "1_1") (pintype "passive"))
      (node (ref "JP33") (pin "2") (pinfunction "2_2") (pintype "passive"))
      (node (ref "JP33") (pin "3") (pinfunction "3_3") (pintype "passive"))
    )
    (net (code "119") (name "Net-(JP34-Pad1)") (class "Default")
      (node (ref "JP34") (pin "1") (pinfunction "1_1") (pintype "passive"))
      (node (ref "JP34") (pin "2") (pinfunction "2_2") (pintype "passive"))
      (node (ref "JP34") (pin "3") (pinfunction "3_3") (pintype "passive"))
    )
    (net (code "120") (name "Net-(JP35-Pad1)") (class "Default")
      (node (ref "JP35") (pin "1") (pinfunction "1_1") (pintype "passive"))
      (node (ref "JP35") (pin "2") (pinfunction "2_2") (pintype "passive"))
      (node (ref "JP35") (pin "3") (pinfunction "3_3") (pintype "passive"))
    )
    (net (code "121") (name "Net-(JP36-Pad1)") (class "Default")
      (node (ref "JP36") (pin "1") (pinfunction "1_1") (pintype "passive"))
      (node (ref "JP36") (pin "2") (pinfunction "2_2") (pintype "passive"))
      (node (ref "JP36") (pin "3") (pinfunction "3_3") (pintype "passive"))
    )
    (net (code "122") (name "Net-(JP37-Pad1)") (class "Default")
      (node (ref "JP37") (pin "1") (pinfunction "1_1") (pintype "passive"))
      (node (ref "JP37") (pin "2") (pinfunction "2_2") (pintype "passive"))
      (node (ref "JP37") (pin "3") (pinfunction "3_3") (pintype "passive"))
    )
    (net (code "123") (name "Net-(JP38-Pad1)") (class "Default")
      (node (ref "JP38") (pin "1") (pinfunction "1_1") (pintype "passive"))
      (node (ref "JP38") (pin "2") (pinfunction "2_2") (pintype "passive"))
      (node (ref "JP38") (pin "3") (pinfunction "3_3") (pintype "passive"))
    )
    (net (code "124") (name "Net-(JP39-Pad1)") (class "Default")
      (node (ref "JP39") (pin "1") (pinfunction "1_1") (pintype "passive"))
      (node (ref "JP39") (pin "2") (pinfunction "2_2") (pintype "passive"))
      (node (ref "JP39") (pin "3") (pinfunction "3_3") (pintype "passive"))
    )
    (net (code "125") (name "Net-(JP40-Pad1)") (class "Default")
      (node (ref "JP40") (pin "1") (pinfunction "1_1") (pintype "passive"))
      (node (ref "JP40") (pin "2") (pinfunction "2_2") (pintype "passive"))
      (node (ref "JP40") (pin "3") (pinfunction "3_3") (pintype "passive"))
    )
    (net (code "126") (name "Net-(JP41-Pad1)") (class "Default")
      (node (ref "JP41") (pin "1") (pinfunction "1_1") (pintype "passive"))
      (node (ref "JP41") (pin "2") (pinfunction "2_2") (pintype "passive"))
      (node (ref "JP41") (pin "3") (pinfunction "3_3") (pintype "passive"))
    )
    (net (code "127") (name "Net-(JP42-Pad1)") (class "Default")
      (node (ref "JP42") (pin "1") (pinfunction "1_1") (pintype "passive"))
      (node (ref "JP42") (pin "2") (pinfunction "2_2") (pintype "passive"))
      (node (ref "JP42") (pin "3") (pinfunction "3_3") (pintype "passive"))
    )
    (net (code "128") (name "Net-(JP43-Pad1)") (class "Default")
      (node (ref "JP43") (pin "1") (pinfunction "1_1") (pintype "passive"))
      (node (ref "JP43") (pin "2") (pinfunction "2_2") (pintype "passive"))
      (node (ref "JP43") (pin "3") (pinfunction "3_3") (pintype "passive"))
    )
    (net (code "129") (name "Net-(JP44-Pad1)") (class "Default")
      (node (ref "JP44") (pin "1") (pinfunction "1_1") (pintype "passive"))
      (node (ref "JP44") (pin "2") (pinfunction "2_2") (pintype "passive"))
      (node (ref "JP44") (pin "3") (pinfunction "3_3") (pintype "passive"))
    )
    (net (code "130") (name "Net-(JP45-Pad1)") (class "Default")
      (node (ref "JP45") (pin "1") (pinfunction "1_1") (pintype "passive"))
      (node (ref "JP45") (pin "2") (pinfunction "2_2") (pintype "passive"))
      (node (ref "JP45") (pin "3") (pinfunction "3_3") (pintype "passive"))
    )
    (net (code "131") (name "Net-(JP46-Pad1)") (class "Default")
      (node (ref "JP46") (pin "1") (pinfunction "1_1") (pintype "passive"))
      (node (ref "JP46") (pin "2") (pinfunction "2_2") (pintype "passive"))
      (node (ref "JP46") (pin "3") (pinfunction "3_3") (pintype "passive"))
    )
    (net (code "132") (name "Net-(JP47-Pad1)") (class "Default")
      (node (ref "JP47") (pin "1") (pinfunction "1_1") (pintype "passive"))
      (node (ref "JP47") (pin "2") (pinfunction "2_2") (pintype "passive"))
      (node (ref "JP47") (pin "3") (pinfunction "3_3") (pintype "passive"))
    )
    (net (code "133") (name "Net-(JP48-Pad1)") (class "Default")
      (node (ref "JP48") (pin "1") (pinfunction "1_1") (pintype "passive"))
      (node (ref "JP48") (pin "2") (pinfunction "2_2") (pintype "passive"))
      (node (ref "JP48") (pin "3") (pinfunction "3_3") (pintype "passive"))
    )
    (net (code "134") (name "Net-(JP49-Pad1)") (class "Default")
      (node (ref "JP49") (pin "1") (pinfunction "1_1") (pintype "passive"))
      (node (ref "JP49") (pin "2") (pinfunction "2_2") (pintype "passive"))
      (node (ref "JP49") (pin "3") (pinfunction "3_3") (pintype "passive"))
    )
    (net (code "135") (name "Net-(JP50-Pad1)") (class "Default")
      (node (ref "JP50") (pin "1") (pinfunction "1_1") (pintype "passive"))
      (node (ref "JP50") (pin "2") (pinfunction "2_2") (pintype "passive"))
      (node (ref "JP50") (pin "3") (pinfunction "3_3") (pintype "passive"))
    )
    (net (code "136") (name "Net-(JP51-Pad1)") (class "Default")
      (node (ref "JP51") (pin "1") (pinfunction "1_1") (pintype "passive"))
      (node (ref "JP51") (pin "2") (pinfunction "2_2") (pintype "passive"))
      (node (ref "JP51") (pin "3") (pinfunction "3_3") (pintype "passive"))
    )
    (net (code "137") (name "Net-(JP52-Pad1)") (class "Default")
      (node (ref "JP52") (pin "1") (pinfunction "1_1") (pintype "passive"))
      (node (ref "JP52") (pin "2") (pinfunction "2_2") (pintype "passive"))
      (node (ref "JP52") (pin "3") (pinfunction "3_3") (pintype "passive"))
    )
    (net (code "138") (name "Net-(JP53-Pad1)") (class "Default")
      (node (ref "JP53") (pin "1") (pinfunction "1_1") (pintype "passive"))
      (node (ref "JP53") (pin "2") (pinfunction "2_2") (pintype "passive"))
      (node (ref "JP53") (pin "3") (pinfunction "3_3") (pintype "passive"))
    )
    (net (code "139") (name "Net-(JP54-Pad1)") (class "Default")
      (node (ref "JP54") (pin "1") (pinfunction "1_1") (pintype "passive"))
      (node (ref "JP54") (pin "2") (pinfunction "2_2") (pintype "passive"))
      (node (ref "JP54") (pin "3") (pinfunction "3_3") (pintype "passive"))
    )
    (net (code "140") (name "Net-(JP55-Pad1)") (class "Default")
      (node (ref "JP55") (pin "1") (pinfunction "1_1") (pintype "passive"))
      (node (ref "JP55") (pin "2") (pinfunction "2_2") (pintype "passive"))
      (node (ref "JP55") (pin "3") (pinfunction "3_3") (pintype "passive"))
    )
    (net (code "141") (name "Net-(JP56-Pad1)") (class "Default")
      (node (ref "JP56") (pin "1") (pinfunction "1_1") (pintype "passive"))
      (node (ref "JP56") (pin "2") (pinfunction "2_2") (pintype "passive"))
      (node (ref "JP56") (pin "3") (pinfunction "3_3") (pintype "passive"))
    )
    (net (code "142") (name "Net-(JP57-Pad1)") (class "Default")
      (node (ref "JP57") (pin "1") (pinfunction "1_1") (pintype "passive"))
      (node (ref "JP57") (pin "2") (pinfunction "2_2") (pintype "passive"))
      (node (ref "JP57") (pin "3") (pinfunction "3_3") (pintype "passive"))
    )
    (net (code "143") (name "Net-(JP58-Pad1)") (class "Default")
      (node (ref "JP58") (pin "1") (pinfunction "1_1") (pintype "passive"))
      (node (ref "JP58") (pin "2") (pinfunction "2_2") (pintype "passive"))
      (node (ref "JP58") (pin "3") (pinfunction "3_3") (pintype "passive"))
    )
    (net (code "144") (name "Net-(JP60-Pad1)") (class "Default")
      (node (ref "JP60") (pin "1") (pinfunction "1_1") (pintype "passive"))
      (node (ref "JP60") (pin "2") (pinfunction "2_2") (pintype "passive"))
      (node (ref "JP60") (pin "3") (pinfunction "3_3") (pintype "passive"))
    )
    (net (code "145") (name "Net-(LED_5VA-PadA)") (class "Default")
      (node (ref "LED_5VA") (pin "A") (pinfunction "A_A") (pintype "passive"))
      (node (ref "R1") (pin "1") (pinfunction "1_1") (pintype "passive"))
    )
    (net (code "146") (name "Net-(LED_5VB-PadA)") (class "Default")
      (node (ref "LED_5VB") (pin "A") (pinfunction "A_A") (pintype "passive"))
      (node (ref "R2") (pin "1") (pinfunction "1_1") (pintype "passive"))
    )
    (net (code "147") (name "Net-(LED_BOOST-PadA)") (class "Default")
      (node (ref "LED_BOOST") (pin "A") (pinfunction "A_A") (pintype "passive"))
      (node (ref "R7") (pin "1") (pinfunction "1_1") (pintype "passive"))
      (node (ref "R8") (pin "1") (pinfunction "1_1") (pintype "passive"))
    )
    (net (code "148") (name "Net-(LED_IG1-PadA)") (class "Default")
      (node (ref "LED_IG1") (pin "A") (pinfunction "A_A") (pintype "passive"))
      (node (ref "R12") (pin "1") (pinfunction "1_1") (pintype "passive"))
    )
    (net (code "149") (name "Net-(Q1-G)") (class "Default")
      (node (ref "Q1") (pin "1") (pinfunction "G_1") (pintype "passive"))
      (node (ref "Q3") (pin "3") (pinfunction "D_3") (pintype "passive"))
      (node (ref "R13") (pin "1") (pinfunction "1_1") (pintype "passive"))
    )
    (net (code "150") (name "Net-(Q2-D)") (class "Default")
      (node (ref "JP63") (pin "3") (pinfunction "3_3") (pintype "passive"))
      (node (ref "Q2") (pin "3") (pinfunction "D_3") (pintype "passive"))
      (node (ref "VBU") (pin "2") (pinfunction "P_2") (pintype "passive"))
    )
    (net (code "151") (name "Net-(Q2-G)") (class "Default")
      (node (ref "Q2") (pin "1") (pinfunction "G_1") (pintype "passive"))
      (node (ref "Q4") (pin "3") (pinfunction "D_3") (pintype "passive"))
      (node (ref "R14") (pin "1") (pinfunction "1_1") (pintype "passive"))
    )
    (net (code "152") (name "Net-(Q5-G)") (class "Default")
      (node (ref "Q5") (pin "1") (pinfunction "G_1") (pintype "passive"))
      (node (ref "Q7") (pin "3") (pinfunction "D_3") (pintype "passive"))
      (node (ref "R17") (pin "1") (pinfunction "1_1") (pintype "passive"))
    )
    (net (code "153") (name "Net-(R7-Pad2)") (class "Default")
      (node (ref "R7") (pin "2") (pinfunction "2_2") (pintype "passive"))
      (node (ref "R9") (pin "1") (pinfunction "1_1") (pintype "passive"))
    )
    (net (code "154") (name "Net-(R10-Pad1)") (class "Default")
      (node (ref "R10") (pin "1") (pinfunction "1_1") (pintype "passive"))
      (node (ref "R8") (pin "2") (pinfunction "2_2") (pintype "passive"))
    )
    (net (code "155") (name "Net-(U$1-SCL)") (class "Default")
      (node (ref "JP10") (pin "8") (pinfunction "8_8") (pintype "passive"))
      (node (ref "U$1") (pin "P$2") (pinfunction "SCL_P$2") (pintype "bidirectional"))
    )
    (net (code "156") (name "Net-(U$1-SDA)") (class "Default")
      (node (ref "JP10") (pin "9") (pinfunction "9_9") (pintype "passive"))
      (node (ref "U$1") (pin "P$3") (pinfunction "SDA_P$3") (pintype "bidirectional"))
    )
    (net (code "157") (name "unconnected-(H/L-S-Pad3)") (class "Default")
      (node (ref "H/L") (pin "3") (pinfunction "S_3") (pintype "passive"))
    )
    (net (code "158") (name "unconnected-(IG1-O-Pad1)") (class "Default")
      (node (ref "IG1") (pin "1") (pinfunction "O_1") (pintype "passive"))
    )
    (net (code "159") (name "unconnected-(JP10-Pad1)") (class "Default")
      (node (ref "JP10") (pin "1") (pinfunction "1_1") (pintype "passive"))
    )
    (net (code "160") (name "unconnected-(JP10-Pad12)") (class "Default")
      (node (ref "JP10") (pin "12") (pinfunction "12_12") (pintype "passive"))
    )
    (net (code "161") (name "unconnected-(JP10-Pad13)") (class "Default")
      (node (ref "JP10") (pin "13") (pinfunction "13_13") (pintype "passive"))
    )
    (net (code "162") (name "unconnected-(JP16-Pad1)") (class "Default")
      (node (ref "JP16") (pin "1") (pinfunction "1_1") (pintype "passive"))
    )
    (net (code "163") (name "unconnected-(JP16-Pad7)") (class "Default")
      (node (ref "JP16") (pin "7") (pinfunction "7_7") (pintype "passive"))
    )
    (net (code "164") (name "unconnected-(JP16-Pad8)") (class "Default")
      (node (ref "JP16") (pin "8") (pinfunction "8_8") (pintype "passive"))
    )
    (net (code "165") (name "unconnected-(JP16-Pad9)") (class "Default")
      (node (ref "JP16") (pin "9") (pinfunction "9_9") (pintype "passive"))
    )
    (net (code "166") (name "unconnected-(JP16-Pad10)") (class "Default")
      (node (ref "JP16") (pin "10") (pinfunction "10_10") (pintype "passive"))
    )
    (net (code "167") (name "unconnected-(JP16-Pad15)") (class "Default")
      (node (ref "JP16") (pin "15") (pinfunction "15_15") (pintype "passive"))
    )
    (net (code "168") (name "unconnected-(JP63-Pad4)") (class "Default")
      (node (ref "JP63") (pin "4") (pinfunction "4_4") (pintype "passive"))
    )
    (net (code "169") (name "unconnected-(TURN-S-Pad3)") (class "Default")
      (node (ref "TURN") (pin "3") (pinfunction "S_3") (pintype "passive"))
    )
    (net (code "170") (name "unconnected-(U$1-LDAC-PadP$4)") (class "Default")
      (node (ref "U$1") (pin "P$4") (pinfunction "LDAC_P$4") (pintype "bidirectional"))
    )
    (net (code "171") (name "unconnected-(U$1-RDY{slash}BSY-PadP$5)") (class "Default")
      (node (ref "U$1") (pin "P$5") (pinfunction "RDY/BSY_P$5") (pintype "bidirectional"))
    )
    (net (code "172") (name "unconnected-(VBU-O-Pad1)") (class "Default")
      (node (ref "VBU") (pin "1") (pinfunction "O_1") (pintype "passive"))
    )
  )
)
